# Core_Power_Decoupling.net
KiCad netlist of a schematic drawn in Altium Designer
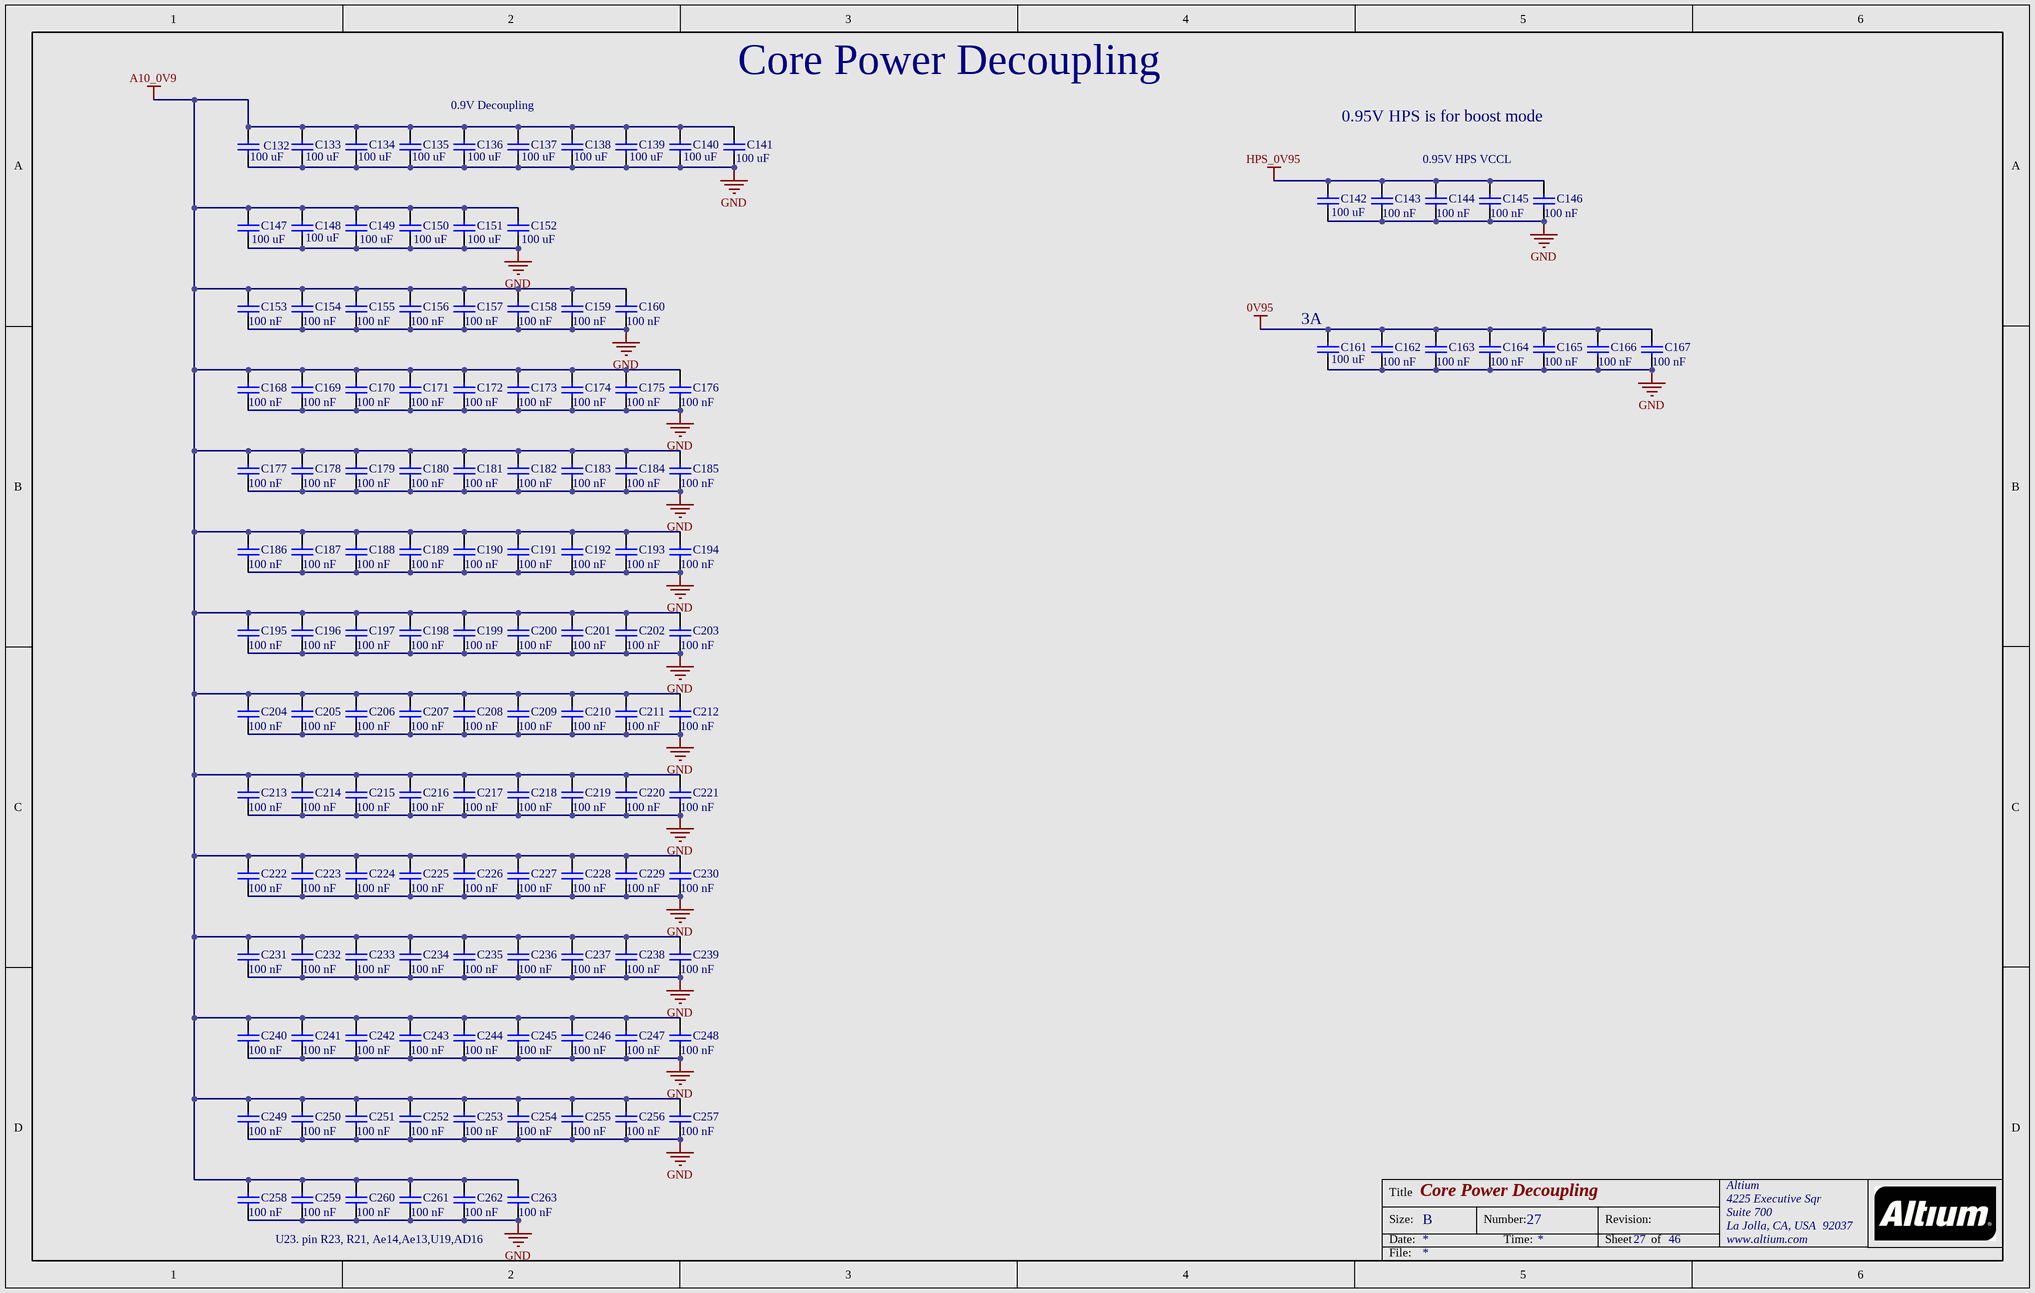
[diagram p0: Core_Power_Decoupling.SchDoc]

(export (version "E")
  (design (tool "Eeschema 10.0.6"))
  (components
    (comp (ref "C132")
      (value "GRM31CR60J107ME39L")
      (footprint "CAPC3216X190X55ML30T25")
      (description "Chip Capacitor, 100 uF, +/- 20%, 6.3 V, -55 to 85 degC, 1206 (3216 Metric), RoHS, Tape and Reel")
      (fields (field (name "TOLERANCE") "20%") (field (name "CAPACITANCE") "100 uF"))
      (libsource (lib "Altium Content Vault") (part "CAP-NP-2"))
    )
    (comp (ref "C133")
      (value "GRM31CR60J107ME39L")
      (footprint "CAPC3216X190X55ML30T25")
      (description "Chip Capacitor, 100 uF, +/- 20%, 6.3 V, -55 to 85 degC, 1206 (3216 Metric), RoHS, Tape and Reel")
      (fields (field (name "TOLERANCE") "20%") (field (name "CAPACITANCE") "100 uF"))
      (libsource (lib "Altium Content Vault") (part "CAP-NP-2"))
    )
    (comp (ref "C134")
      (value "GRM31CR60J107ME39L")
      (footprint "CAPC3216X190X55ML30T25")
      (description "Chip Capacitor, 100 uF, +/- 20%, 6.3 V, -55 to 85 degC, 1206 (3216 Metric), RoHS, Tape and Reel")
      (fields (field (name "TOLERANCE") "20%") (field (name "CAPACITANCE") "100 uF"))
      (libsource (lib "Altium Content Vault") (part "CAP-NP-2"))
    )
    (comp (ref "C135")
      (value "GRM31CR60J107ME39L")
      (footprint "CAPC3216X190X55ML30T25")
      (description "Chip Capacitor, 100 uF, +/- 20%, 6.3 V, -55 to 85 degC, 1206 (3216 Metric), RoHS, Tape and Reel")
      (fields (field (name "TOLERANCE") "20%") (field (name "CAPACITANCE") "100 uF"))
      (libsource (lib "Altium Content Vault") (part "CAP-NP-2"))
    )
    (comp (ref "C136")
      (value "GRM31CR60J107ME39L")
      (footprint "CAPC3216X190X55ML30T25")
      (description "Chip Capacitor, 100 uF, +/- 20%, 6.3 V, -55 to 85 degC, 1206 (3216 Metric), RoHS, Tape and Reel")
      (fields (field (name "TOLERANCE") "20%") (field (name "CAPACITANCE") "100 uF"))
      (libsource (lib "Altium Content Vault") (part "CAP-NP-2"))
    )
    (comp (ref "C137")
      (value "GRM31CR60J107ME39L")
      (footprint "CAPC3216X190X55ML30T25")
      (description "Chip Capacitor, 100 uF, +/- 20%, 6.3 V, -55 to 85 degC, 1206 (3216 Metric), RoHS, Tape and Reel")
      (fields (field (name "TOLERANCE") "20%") (field (name "CAPACITANCE") "100 uF"))
      (libsource (lib "Altium Content Vault") (part "CAP-NP-2"))
    )
    (comp (ref "C138")
      (value "GRM31CR60J107ME39L")
      (footprint "CAPC3216X190X55ML30T25")
      (description "Chip Capacitor, 100 uF, +/- 20%, 6.3 V, -55 to 85 degC, 1206 (3216 Metric), RoHS, Tape and Reel")
      (fields (field (name "TOLERANCE") "20%") (field (name "CAPACITANCE") "100 uF"))
      (libsource (lib "Altium Content Vault") (part "CAP-NP-2"))
    )
    (comp (ref "C139")
      (value "GRM31CR60J107ME39L")
      (footprint "CAPC3216X190X55ML30T25")
      (description "Chip Capacitor, 100 uF, +/- 20%, 6.3 V, -55 to 85 degC, 1206 (3216 Metric), RoHS, Tape and Reel")
      (fields (field (name "TOLERANCE") "20%") (field (name "CAPACITANCE") "100 uF"))
      (libsource (lib "Altium Content Vault") (part "CAP-NP-2"))
    )
    (comp (ref "C140")
      (value "GRM31CR60J107ME39L")
      (footprint "CAPC3216X190X55ML30T25")
      (description "Chip Capacitor, 100 uF, +/- 20%, 6.3 V, -55 to 85 degC, 1206 (3216 Metric), RoHS, Tape and Reel")
      (fields (field (name "TOLERANCE") "20%") (field (name "CAPACITANCE") "100 uF"))
      (libsource (lib "Altium Content Vault") (part "CAP-NP-2"))
    )
    (comp (ref "C141")
      (value "GRM31CR60J107ME39L")
      (footprint "CAPC3216X190X55ML30T25")
      (description "Chip Capacitor, 100 uF, +/- 20%, 6.3 V, -55 to 85 degC, 1206 (3216 Metric), RoHS, Tape and Reel")
      (fields (field (name "TOLERANCE") "20%") (field (name "CAPACITANCE") "100 uF"))
      (libsource (lib "Altium Content Vault") (part "CAP-NP-2"))
    )
    (comp (ref "C142")
      (value "GRM31CR60J107ME39L")
      (footprint "CAPC3216X190X55ML30T25")
      (description "Chip Capacitor, 100 uF, +/- 20%, 6.3 V, -55 to 85 degC, 1206 (3216 Metric), RoHS, Tape and Reel")
      (fields (field (name "TOLERANCE") "20%") (field (name "CAPACITANCE") "100 uF"))
      (libsource (lib "Altium Content Vault") (part "CAP-NP-2"))
    )
    (comp (ref "C143")
      (value "GRM033R60J104KE19D")
      (footprint "CAPC0603X33X15LL03T05")
      (description "Chip Capacitor, 100 nF, +/- 10%, 6.3 V, -55 to 85 degC, 0201 (0603 Metric), RoHS, Tape and Reel")
      (fields
        (field (name "TOLERANCE") "10%")
        (field (name "CAPACITANCE") "100 nF")
        (field (name "MANUFACTURER") "Basic Passives")
      )
      (libsource (lib "Altium Content Vault") (part "CAP-NP-2"))
    )
    (comp (ref "C144")
      (value "GRM033R60J104KE19D")
      (footprint "CAPC0603X33X15LL03T05")
      (description "Chip Capacitor, 100 nF, +/- 10%, 6.3 V, -55 to 85 degC, 0201 (0603 Metric), RoHS, Tape and Reel")
      (fields
        (field (name "TOLERANCE") "10%")
        (field (name "CAPACITANCE") "100 nF")
        (field (name "MANUFACTURER") "Basic Passives")
      )
      (libsource (lib "Altium Content Vault") (part "CAP-NP-2"))
    )
    (comp (ref "C145")
      (value "GRM033R60J104KE19D")
      (footprint "CAPC0603X33X15LL03T05")
      (description "Chip Capacitor, 100 nF, +/- 10%, 6.3 V, -55 to 85 degC, 0201 (0603 Metric), RoHS, Tape and Reel")
      (fields
        (field (name "TOLERANCE") "10%")
        (field (name "CAPACITANCE") "100 nF")
        (field (name "MANUFACTURER") "Basic Passives")
      )
      (libsource (lib "Altium Content Vault") (part "CAP-NP-2"))
    )
    (comp (ref "C146")
      (value "GRM033R60J104KE19D")
      (footprint "CAPC0603X33X15LL03T05")
      (description "Chip Capacitor, 100 nF, +/- 10%, 6.3 V, -55 to 85 degC, 0201 (0603 Metric), RoHS, Tape and Reel")
      (fields
        (field (name "TOLERANCE") "10%")
        (field (name "CAPACITANCE") "100 nF")
        (field (name "MANUFACTURER") "Basic Passives")
      )
      (libsource (lib "Altium Content Vault") (part "CAP-NP-2"))
    )
    (comp (ref "C147")
      (value "GRM31CR60J107ME39L")
      (footprint "CAPC3216X190X55ML30T25")
      (description "Chip Capacitor, 100 uF, +/- 20%, 6.3 V, -55 to 85 degC, 1206 (3216 Metric), RoHS, Tape and Reel")
      (fields (field (name "TOLERANCE") "20%") (field (name "CAPACITANCE") "100 uF"))
      (libsource (lib "Altium Content Vault") (part "CAP-NP-2"))
    )
    (comp (ref "C148")
      (value "GRM31CR60J107ME39L")
      (footprint "CAPC3216X190X55ML30T25")
      (description "Chip Capacitor, 100 uF, +/- 20%, 6.3 V, -55 to 85 degC, 1206 (3216 Metric), RoHS, Tape and Reel")
      (fields (field (name "TOLERANCE") "20%") (field (name "CAPACITANCE") "100 uF"))
      (libsource (lib "Altium Content Vault") (part "CAP-NP-2"))
    )
    (comp (ref "C149")
      (value "GRM31CR60J107ME39L")
      (footprint "CAPC3216X190X55ML30T25")
      (description "Chip Capacitor, 100 uF, +/- 20%, 6.3 V, -55 to 85 degC, 1206 (3216 Metric), RoHS, Tape and Reel")
      (fields (field (name "TOLERANCE") "20%") (field (name "CAPACITANCE") "100 uF"))
      (libsource (lib "Altium Content Vault") (part "CAP-NP-2"))
    )
    (comp (ref "C150")
      (value "GRM31CR60J107ME39L")
      (footprint "CAPC3216X190X55ML30T25")
      (description "Chip Capacitor, 100 uF, +/- 20%, 6.3 V, -55 to 85 degC, 1206 (3216 Metric), RoHS, Tape and Reel")
      (fields (field (name "TOLERANCE") "20%") (field (name "CAPACITANCE") "100 uF"))
      (libsource (lib "Altium Content Vault") (part "CAP-NP-2"))
    )
    (comp (ref "C151")
      (value "GRM31CR60J107ME39L")
      (footprint "CAPC3216X190X55ML30T25")
      (description "Chip Capacitor, 100 uF, +/- 20%, 6.3 V, -55 to 85 degC, 1206 (3216 Metric), RoHS, Tape and Reel")
      (fields (field (name "TOLERANCE") "20%") (field (name "CAPACITANCE") "100 uF"))
      (libsource (lib "Altium Content Vault") (part "CAP-NP-2"))
    )
    (comp (ref "C152")
      (value "GRM31CR60J107ME39L")
      (footprint "CAPC3216X190X55ML30T25")
      (description "Chip Capacitor, 100 uF, +/- 20%, 6.3 V, -55 to 85 degC, 1206 (3216 Metric), RoHS, Tape and Reel")
      (fields (field (name "TOLERANCE") "20%") (field (name "CAPACITANCE") "100 uF"))
      (libsource (lib "Altium Content Vault") (part "CAP-NP-2"))
    )
    (comp (ref "C153")
      (value "GRM033R60J104KE19D")
      (footprint "CAPC0603X33X15LL03T05")
      (description "Chip Capacitor, 100 nF, +/- 10%, 6.3 V, -55 to 85 degC, 0201 (0603 Metric), RoHS, Tape and Reel")
      (fields
        (field (name "TOLERANCE") "10%")
        (field (name "CAPACITANCE") "100 nF")
        (field (name "MANUFACTURER") "Basic Passives")
      )
      (libsource (lib "Altium Content Vault") (part "CAP-NP-2"))
    )
    (comp (ref "C154")
      (value "GRM033R60J104KE19D")
      (footprint "CAPC0603X33X15LL03T05")
      (description "Chip Capacitor, 100 nF, +/- 10%, 6.3 V, -55 to 85 degC, 0201 (0603 Metric), RoHS, Tape and Reel")
      (fields
        (field (name "TOLERANCE") "10%")
        (field (name "CAPACITANCE") "100 nF")
        (field (name "MANUFACTURER") "Basic Passives")
      )
      (libsource (lib "Altium Content Vault") (part "CAP-NP-2"))
    )
    (comp (ref "C155")
      (value "GRM033R60J104KE19D")
      (footprint "CAPC0603X33X15LL03T05")
      (description "Chip Capacitor, 100 nF, +/- 10%, 6.3 V, -55 to 85 degC, 0201 (0603 Metric), RoHS, Tape and Reel")
      (fields
        (field (name "TOLERANCE") "10%")
        (field (name "CAPACITANCE") "100 nF")
        (field (name "MANUFACTURER") "Basic Passives")
      )
      (libsource (lib "Altium Content Vault") (part "CAP-NP-2"))
    )
    (comp (ref "C156")
      (value "GRM033R60J104KE19D")
      (footprint "CAPC0603X33X15LL03T05")
      (description "Chip Capacitor, 100 nF, +/- 10%, 6.3 V, -55 to 85 degC, 0201 (0603 Metric), RoHS, Tape and Reel")
      (fields
        (field (name "TOLERANCE") "10%")
        (field (name "CAPACITANCE") "100 nF")
        (field (name "MANUFACTURER") "Basic Passives")
      )
      (libsource (lib "Altium Content Vault") (part "CAP-NP-2"))
    )
    (comp (ref "C157")
      (value "GRM033R60J104KE19D")
      (footprint "CAPC0603X33X15LL03T05")
      (description "Chip Capacitor, 100 nF, +/- 10%, 6.3 V, -55 to 85 degC, 0201 (0603 Metric), RoHS, Tape and Reel")
      (fields
        (field (name "TOLERANCE") "10%")
        (field (name "CAPACITANCE") "100 nF")
        (field (name "MANUFACTURER") "Basic Passives")
      )
      (libsource (lib "Altium Content Vault") (part "CAP-NP-2"))
    )
    (comp (ref "C158")
      (value "GRM033R60J104KE19D")
      (footprint "CAPC0603X33X15LL03T05")
      (description "Chip Capacitor, 100 nF, +/- 10%, 6.3 V, -55 to 85 degC, 0201 (0603 Metric), RoHS, Tape and Reel")
      (fields
        (field (name "TOLERANCE") "10%")
        (field (name "CAPACITANCE") "100 nF")
        (field (name "MANUFACTURER") "Basic Passives")
      )
      (libsource (lib "Altium Content Vault") (part "CAP-NP-2"))
    )
    (comp (ref "C159")
      (value "GRM033R60J104KE19D")
      (footprint "CAPC0603X33X15LL03T05")
      (description "Chip Capacitor, 100 nF, +/- 10%, 6.3 V, -55 to 85 degC, 0201 (0603 Metric), RoHS, Tape and Reel")
      (fields
        (field (name "TOLERANCE") "10%")
        (field (name "CAPACITANCE") "100 nF")
        (field (name "MANUFACTURER") "Basic Passives")
      )
      (libsource (lib "Altium Content Vault") (part "CAP-NP-2"))
    )
    (comp (ref "C160")
      (value "GRM033R60J104KE19D")
      (footprint "CAPC0603X33X15LL03T05")
      (description "Chip Capacitor, 100 nF, +/- 10%, 6.3 V, -55 to 85 degC, 0201 (0603 Metric), RoHS, Tape and Reel")
      (fields
        (field (name "TOLERANCE") "10%")
        (field (name "CAPACITANCE") "100 nF")
        (field (name "MANUFACTURER") "Basic Passives")
      )
      (libsource (lib "Altium Content Vault") (part "CAP-NP-2"))
    )
    (comp (ref "C161")
      (value "GRM31CR60J107ME39L")
      (footprint "CAPC3216X190X55ML30T25")
      (description "Chip Capacitor, 100 uF, +/- 20%, 6.3 V, -55 to 85 degC, 1206 (3216 Metric), RoHS, Tape and Reel")
      (fields (field (name "TOLERANCE") "20%") (field (name "CAPACITANCE") "100 uF"))
      (libsource (lib "Altium Content Vault") (part "CAP-NP-2"))
    )
    (comp (ref "C162")
      (value "GRM033R60J104KE19D")
      (footprint "CAPC0603X33X15LL03T05")
      (description "Chip Capacitor, 100 nF, +/- 10%, 6.3 V, -55 to 85 degC, 0201 (0603 Metric), RoHS, Tape and Reel")
      (fields
        (field (name "TOLERANCE") "10%")
        (field (name "CAPACITANCE") "100 nF")
        (field (name "MANUFACTURER") "Basic Passives")
      )
      (libsource (lib "Altium Content Vault") (part "CAP-NP-2"))
    )
    (comp (ref "C163")
      (value "GRM033R60J104KE19D")
      (footprint "CAPC0603X33X15LL03T05")
      (description "Chip Capacitor, 100 nF, +/- 10%, 6.3 V, -55 to 85 degC, 0201 (0603 Metric), RoHS, Tape and Reel")
      (fields
        (field (name "TOLERANCE") "10%")
        (field (name "CAPACITANCE") "100 nF")
        (field (name "MANUFACTURER") "Basic Passives")
      )
      (libsource (lib "Altium Content Vault") (part "CAP-NP-2"))
    )
    (comp (ref "C164")
      (value "GRM033R60J104KE19D")
      (footprint "CAPC0603X33X15LL03T05")
      (description "Chip Capacitor, 100 nF, +/- 10%, 6.3 V, -55 to 85 degC, 0201 (0603 Metric), RoHS, Tape and Reel")
      (fields
        (field (name "TOLERANCE") "10%")
        (field (name "CAPACITANCE") "100 nF")
        (field (name "MANUFACTURER") "Basic Passives")
      )
      (libsource (lib "Altium Content Vault") (part "CAP-NP-2"))
    )
    (comp (ref "C165")
      (value "GRM033R60J104KE19D")
      (footprint "CAPC0603X33X15LL03T05")
      (description "Chip Capacitor, 100 nF, +/- 10%, 6.3 V, -55 to 85 degC, 0201 (0603 Metric), RoHS, Tape and Reel")
      (fields
        (field (name "TOLERANCE") "10%")
        (field (name "CAPACITANCE") "100 nF")
        (field (name "MANUFACTURER") "Basic Passives")
      )
      (libsource (lib "Altium Content Vault") (part "CAP-NP-2"))
    )
    (comp (ref "C166")
      (value "GRM033R60J104KE19D")
      (footprint "CAPC0603X33X15LL03T05")
      (description "Chip Capacitor, 100 nF, +/- 10%, 6.3 V, -55 to 85 degC, 0201 (0603 Metric), RoHS, Tape and Reel")
      (fields
        (field (name "TOLERANCE") "10%")
        (field (name "CAPACITANCE") "100 nF")
        (field (name "MANUFACTURER") "Basic Passives")
      )
      (libsource (lib "Altium Content Vault") (part "CAP-NP-2"))
    )
    (comp (ref "C167")
      (value "GRM033R60J104KE19D")
      (footprint "CAPC0603X33X15LL03T05")
      (description "Chip Capacitor, 100 nF, +/- 10%, 6.3 V, -55 to 85 degC, 0201 (0603 Metric), RoHS, Tape and Reel")
      (fields
        (field (name "TOLERANCE") "10%")
        (field (name "CAPACITANCE") "100 nF")
        (field (name "MANUFACTURER") "Basic Passives")
      )
      (libsource (lib "Altium Content Vault") (part "CAP-NP-2"))
    )
    (comp (ref "C168")
      (value "GRM033R60J104KE19D")
      (footprint "CAPC0603X33X15LL03T05")
      (description "Chip Capacitor, 100 nF, +/- 10%, 6.3 V, -55 to 85 degC, 0201 (0603 Metric), RoHS, Tape and Reel")
      (fields
        (field (name "TOLERANCE") "10%")
        (field (name "CAPACITANCE") "100 nF")
        (field (name "MANUFACTURER") "Basic Passives")
      )
      (libsource (lib "Altium Content Vault") (part "CAP-NP-2"))
    )
    (comp (ref "C169")
      (value "GRM033R60J104KE19D")
      (footprint "CAPC0603X33X15LL03T05")
      (description "Chip Capacitor, 100 nF, +/- 10%, 6.3 V, -55 to 85 degC, 0201 (0603 Metric), RoHS, Tape and Reel")
      (fields
        (field (name "TOLERANCE") "10%")
        (field (name "CAPACITANCE") "100 nF")
        (field (name "MANUFACTURER") "Basic Passives")
      )
      (libsource (lib "Altium Content Vault") (part "CAP-NP-2"))
    )
    (comp (ref "C170")
      (value "GRM033R60J104KE19D")
      (footprint "CAPC0603X33X15LL03T05")
      (description "Chip Capacitor, 100 nF, +/- 10%, 6.3 V, -55 to 85 degC, 0201 (0603 Metric), RoHS, Tape and Reel")
      (fields
        (field (name "TOLERANCE") "10%")
        (field (name "CAPACITANCE") "100 nF")
        (field (name "MANUFACTURER") "Basic Passives")
      )
      (libsource (lib "Altium Content Vault") (part "CAP-NP-2"))
    )
    (comp (ref "C171")
      (value "GRM033R60J104KE19D")
      (footprint "CAPC0603X33X15LL03T05")
      (description "Chip Capacitor, 100 nF, +/- 10%, 6.3 V, -55 to 85 degC, 0201 (0603 Metric), RoHS, Tape and Reel")
      (fields
        (field (name "TOLERANCE") "10%")
        (field (name "CAPACITANCE") "100 nF")
        (field (name "MANUFACTURER") "Basic Passives")
      )
      (libsource (lib "Altium Content Vault") (part "CAP-NP-2"))
    )
    (comp (ref "C172")
      (value "GRM033R60J104KE19D")
      (footprint "CAPC0603X33X15LL03T05")
      (description "Chip Capacitor, 100 nF, +/- 10%, 6.3 V, -55 to 85 degC, 0201 (0603 Metric), RoHS, Tape and Reel")
      (fields
        (field (name "TOLERANCE") "10%")
        (field (name "CAPACITANCE") "100 nF")
        (field (name "MANUFACTURER") "Basic Passives")
      )
      (libsource (lib "Altium Content Vault") (part "CAP-NP-2"))
    )
    (comp (ref "C173")
      (value "GRM033R60J104KE19D")
      (footprint "CAPC0603X33X15LL03T05")
      (description "Chip Capacitor, 100 nF, +/- 10%, 6.3 V, -55 to 85 degC, 0201 (0603 Metric), RoHS, Tape and Reel")
      (fields
        (field (name "TOLERANCE") "10%")
        (field (name "CAPACITANCE") "100 nF")
        (field (name "MANUFACTURER") "Basic Passives")
      )
      (libsource (lib "Altium Content Vault") (part "CAP-NP-2"))
    )
    (comp (ref "C174")
      (value "GRM033R60J104KE19D")
      (footprint "CAPC0603X33X15LL03T05")
      (description "Chip Capacitor, 100 nF, +/- 10%, 6.3 V, -55 to 85 degC, 0201 (0603 Metric), RoHS, Tape and Reel")
      (fields
        (field (name "TOLERANCE") "10%")
        (field (name "CAPACITANCE") "100 nF")
        (field (name "MANUFACTURER") "Basic Passives")
      )
      (libsource (lib "Altium Content Vault") (part "CAP-NP-2"))
    )
    (comp (ref "C175")
      (value "GRM033R60J104KE19D")
      (footprint "CAPC0603X33X15LL03T05")
      (description "Chip Capacitor, 100 nF, +/- 10%, 6.3 V, -55 to 85 degC, 0201 (0603 Metric), RoHS, Tape and Reel")
      (fields
        (field (name "TOLERANCE") "10%")
        (field (name "CAPACITANCE") "100 nF")
        (field (name "MANUFACTURER") "Basic Passives")
      )
      (libsource (lib "Altium Content Vault") (part "CAP-NP-2"))
    )
    (comp (ref "C176")
      (value "GRM033R60J104KE19D")
      (footprint "CAPC0603X33X15LL03T05")
      (description "Chip Capacitor, 100 nF, +/- 10%, 6.3 V, -55 to 85 degC, 0201 (0603 Metric), RoHS, Tape and Reel")
      (fields
        (field (name "TOLERANCE") "10%")
        (field (name "CAPACITANCE") "100 nF")
        (field (name "MANUFACTURER") "Basic Passives")
      )
      (libsource (lib "Altium Content Vault") (part "CAP-NP-2"))
    )
    (comp (ref "C177")
      (value "GRM033R60J104KE19D")
      (footprint "CAPC0603X33X15LL03T05")
      (description "Chip Capacitor, 100 nF, +/- 10%, 6.3 V, -55 to 85 degC, 0201 (0603 Metric), RoHS, Tape and Reel")
      (fields
        (field (name "TOLERANCE") "10%")
        (field (name "CAPACITANCE") "100 nF")
        (field (name "MANUFACTURER") "Basic Passives")
      )
      (libsource (lib "Altium Content Vault") (part "CAP-NP-2"))
    )
    (comp (ref "C178")
      (value "GRM033R60J104KE19D")
      (footprint "CAPC0603X33X15LL03T05")
      (description "Chip Capacitor, 100 nF, +/- 10%, 6.3 V, -55 to 85 degC, 0201 (0603 Metric), RoHS, Tape and Reel")
      (fields
        (field (name "TOLERANCE") "10%")
        (field (name "CAPACITANCE") "100 nF")
        (field (name "MANUFACTURER") "Basic Passives")
      )
      (libsource (lib "Altium Content Vault") (part "CAP-NP-2"))
    )
    (comp (ref "C179")
      (value "GRM033R60J104KE19D")
      (footprint "CAPC0603X33X15LL03T05")
      (description "Chip Capacitor, 100 nF, +/- 10%, 6.3 V, -55 to 85 degC, 0201 (0603 Metric), RoHS, Tape and Reel")
      (fields
        (field (name "TOLERANCE") "10%")
        (field (name "CAPACITANCE") "100 nF")
        (field (name "MANUFACTURER") "Basic Passives")
      )
      (libsource (lib "Altium Content Vault") (part "CAP-NP-2"))
    )
    (comp (ref "C180")
      (value "GRM033R60J104KE19D")
      (footprint "CAPC0603X33X15LL03T05")
      (description "Chip Capacitor, 100 nF, +/- 10%, 6.3 V, -55 to 85 degC, 0201 (0603 Metric), RoHS, Tape and Reel")
      (fields
        (field (name "TOLERANCE") "10%")
        (field (name "CAPACITANCE") "100 nF")
        (field (name "MANUFACTURER") "Basic Passives")
      )
      (libsource (lib "Altium Content Vault") (part "CAP-NP-2"))
    )
    (comp (ref "C181")
      (value "GRM033R60J104KE19D")
      (footprint "CAPC0603X33X15LL03T05")
      (description "Chip Capacitor, 100 nF, +/- 10%, 6.3 V, -55 to 85 degC, 0201 (0603 Metric), RoHS, Tape and Reel")
      (fields
        (field (name "TOLERANCE") "10%")
        (field (name "CAPACITANCE") "100 nF")
        (field (name "MANUFACTURER") "Basic Passives")
      )
      (libsource (lib "Altium Content Vault") (part "CAP-NP-2"))
    )
    (comp (ref "C182")
      (value "GRM033R60J104KE19D")
      (footprint "CAPC0603X33X15LL03T05")
      (description "Chip Capacitor, 100 nF, +/- 10%, 6.3 V, -55 to 85 degC, 0201 (0603 Metric), RoHS, Tape and Reel")
      (fields
        (field (name "TOLERANCE") "10%")
        (field (name "CAPACITANCE") "100 nF")
        (field (name "MANUFACTURER") "Basic Passives")
      )
      (libsource (lib "Altium Content Vault") (part "CAP-NP-2"))
    )
    (comp (ref "C183")
      (value "GRM033R60J104KE19D")
      (footprint "CAPC0603X33X15LL03T05")
      (description "Chip Capacitor, 100 nF, +/- 10%, 6.3 V, -55 to 85 degC, 0201 (0603 Metric), RoHS, Tape and Reel")
      (fields
        (field (name "TOLERANCE") "10%")
        (field (name "CAPACITANCE") "100 nF")
        (field (name "MANUFACTURER") "Basic Passives")
      )
      (libsource (lib "Altium Content Vault") (part "CAP-NP-2"))
    )
    (comp (ref "C184")
      (value "GRM033R60J104KE19D")
      (footprint "CAPC0603X33X15LL03T05")
      (description "Chip Capacitor, 100 nF, +/- 10%, 6.3 V, -55 to 85 degC, 0201 (0603 Metric), RoHS, Tape and Reel")
      (fields
        (field (name "TOLERANCE") "10%")
        (field (name "CAPACITANCE") "100 nF")
        (field (name "MANUFACTURER") "Basic Passives")
      )
      (libsource (lib "Altium Content Vault") (part "CAP-NP-2"))
    )
    (comp (ref "C185")
      (value "GRM033R60J104KE19D")
      (footprint "CAPC0603X33X15LL03T05")
      (description "Chip Capacitor, 100 nF, +/- 10%, 6.3 V, -55 to 85 degC, 0201 (0603 Metric), RoHS, Tape and Reel")
      (fields
        (field (name "TOLERANCE") "10%")
        (field (name "CAPACITANCE") "100 nF")
        (field (name "MANUFACTURER") "Basic Passives")
      )
      (libsource (lib "Altium Content Vault") (part "CAP-NP-2"))
    )
    (comp (ref "C186")
      (value "GRM033R60J104KE19D")
      (footprint "CAPC0603X33X15LL03T05")
      (description "Chip Capacitor, 100 nF, +/- 10%, 6.3 V, -55 to 85 degC, 0201 (0603 Metric), RoHS, Tape and Reel")
      (fields
        (field (name "TOLERANCE") "10%")
        (field (name "CAPACITANCE") "100 nF")
        (field (name "MANUFACTURER") "Basic Passives")
      )
      (libsource (lib "Altium Content Vault") (part "CAP-NP-2"))
    )
    (comp (ref "C187")
      (value "GRM033R60J104KE19D")
      (footprint "CAPC0603X33X15LL03T05")
      (description "Chip Capacitor, 100 nF, +/- 10%, 6.3 V, -55 to 85 degC, 0201 (0603 Metric), RoHS, Tape and Reel")
      (fields
        (field (name "TOLERANCE") "10%")
        (field (name "CAPACITANCE") "100 nF")
        (field (name "MANUFACTURER") "Basic Passives")
      )
      (libsource (lib "Altium Content Vault") (part "CAP-NP-2"))
    )
    (comp (ref "C188")
      (value "GRM033R60J104KE19D")
      (footprint "CAPC0603X33X15LL03T05")
      (description "Chip Capacitor, 100 nF, +/- 10%, 6.3 V, -55 to 85 degC, 0201 (0603 Metric), RoHS, Tape and Reel")
      (fields
        (field (name "TOLERANCE") "10%")
        (field (name "CAPACITANCE") "100 nF")
        (field (name "MANUFACTURER") "Basic Passives")
      )
      (libsource (lib "Altium Content Vault") (part "CAP-NP-2"))
    )
    (comp (ref "C189")
      (value "GRM033R60J104KE19D")
      (footprint "CAPC0603X33X15LL03T05")
      (description "Chip Capacitor, 100 nF, +/- 10%, 6.3 V, -55 to 85 degC, 0201 (0603 Metric), RoHS, Tape and Reel")
      (fields
        (field (name "TOLERANCE") "10%")
        (field (name "CAPACITANCE") "100 nF")
        (field (name "MANUFACTURER") "Basic Passives")
      )
      (libsource (lib "Altium Content Vault") (part "CAP-NP-2"))
    )
    (comp (ref "C190")
      (value "GRM033R60J104KE19D")
      (footprint "CAPC0603X33X15LL03T05")
      (description "Chip Capacitor, 100 nF, +/- 10%, 6.3 V, -55 to 85 degC, 0201 (0603 Metric), RoHS, Tape and Reel")
      (fields
        (field (name "TOLERANCE") "10%")
        (field (name "CAPACITANCE") "100 nF")
        (field (name "MANUFACTURER") "Basic Passives")
      )
      (libsource (lib "Altium Content Vault") (part "CAP-NP-2"))
    )
    (comp (ref "C191")
      (value "GRM033R60J104KE19D")
      (footprint "CAPC0603X33X15LL03T05")
      (description "Chip Capacitor, 100 nF, +/- 10%, 6.3 V, -55 to 85 degC, 0201 (0603 Metric), RoHS, Tape and Reel")
      (fields
        (field (name "TOLERANCE") "10%")
        (field (name "CAPACITANCE") "100 nF")
        (field (name "MANUFACTURER") "Basic Passives")
      )
      (libsource (lib "Altium Content Vault") (part "CAP-NP-2"))
    )
    (comp (ref "C192")
      (value "GRM033R60J104KE19D")
      (footprint "CAPC0603X33X15LL03T05")
      (description "Chip Capacitor, 100 nF, +/- 10%, 6.3 V, -55 to 85 degC, 0201 (0603 Metric), RoHS, Tape and Reel")
      (fields
        (field (name "TOLERANCE") "10%")
        (field (name "CAPACITANCE") "100 nF")
        (field (name "MANUFACTURER") "Basic Passives")
      )
      (libsource (lib "Altium Content Vault") (part "CAP-NP-2"))
    )
    (comp (ref "C193")
      (value "GRM033R60J104KE19D")
      (footprint "CAPC0603X33X15LL03T05")
      (description "Chip Capacitor, 100 nF, +/- 10%, 6.3 V, -55 to 85 degC, 0201 (0603 Metric), RoHS, Tape and Reel")
      (fields
        (field (name "TOLERANCE") "10%")
        (field (name "CAPACITANCE") "100 nF")
        (field (name "MANUFACTURER") "Basic Passives")
      )
      (libsource (lib "Altium Content Vault") (part "CAP-NP-2"))
    )
    (comp (ref "C194")
      (value "GRM033R60J104KE19D")
      (footprint "CAPC0603X33X15LL03T05")
      (description "Chip Capacitor, 100 nF, +/- 10%, 6.3 V, -55 to 85 degC, 0201 (0603 Metric), RoHS, Tape and Reel")
      (fields
        (field (name "TOLERANCE") "10%")
        (field (name "CAPACITANCE") "100 nF")
        (field (name "MANUFACTURER") "Basic Passives")
      )
      (libsource (lib "Altium Content Vault") (part "CAP-NP-2"))
    )
    (comp (ref "C195")
      (value "GRM033R60J104KE19D")
      (footprint "CAPC0603X33X15LL03T05")
      (description "Chip Capacitor, 100 nF, +/- 10%, 6.3 V, -55 to 85 degC, 0201 (0603 Metric), RoHS, Tape and Reel")
      (fields
        (field (name "TOLERANCE") "10%")
        (field (name "CAPACITANCE") "100 nF")
        (field (name "MANUFACTURER") "Basic Passives")
      )
      (libsource (lib "Altium Content Vault") (part "CAP-NP-2"))
    )
    (comp (ref "C196")
      (value "GRM033R60J104KE19D")
      (footprint "CAPC0603X33X15LL03T05")
      (description "Chip Capacitor, 100 nF, +/- 10%, 6.3 V, -55 to 85 degC, 0201 (0603 Metric), RoHS, Tape and Reel")
      (fields
        (field (name "TOLERANCE") "10%")
        (field (name "CAPACITANCE") "100 nF")
        (field (name "MANUFACTURER") "Basic Passives")
      )
      (libsource (lib "Altium Content Vault") (part "CAP-NP-2"))
    )
    (comp (ref "C197")
      (value "GRM033R60J104KE19D")
      (footprint "CAPC0603X33X15LL03T05")
      (description "Chip Capacitor, 100 nF, +/- 10%, 6.3 V, -55 to 85 degC, 0201 (0603 Metric), RoHS, Tape and Reel")
      (fields
        (field (name "TOLERANCE") "10%")
        (field (name "CAPACITANCE") "100 nF")
        (field (name "MANUFACTURER") "Basic Passives")
      )
      (libsource (lib "Altium Content Vault") (part "CAP-NP-2"))
    )
    (comp (ref "C198")
      (value "GRM033R60J104KE19D")
      (footprint "CAPC0603X33X15LL03T05")
      (description "Chip Capacitor, 100 nF, +/- 10%, 6.3 V, -55 to 85 degC, 0201 (0603 Metric), RoHS, Tape and Reel")
      (fields
        (field (name "TOLERANCE") "10%")
        (field (name "CAPACITANCE") "100 nF")
        (field (name "MANUFACTURER") "Basic Passives")
      )
      (libsource (lib "Altium Content Vault") (part "CAP-NP-2"))
    )
    (comp (ref "C199")
      (value "GRM033R60J104KE19D")
      (footprint "CAPC0603X33X15LL03T05")
      (description "Chip Capacitor, 100 nF, +/- 10%, 6.3 V, -55 to 85 degC, 0201 (0603 Metric), RoHS, Tape and Reel")
      (fields
        (field (name "TOLERANCE") "10%")
        (field (name "CAPACITANCE") "100 nF")
        (field (name "MANUFACTURER") "Basic Passives")
      )
      (libsource (lib "Altium Content Vault") (part "CAP-NP-2"))
    )
    (comp (ref "C200")
      (value "GRM033R60J104KE19D")
      (footprint "CAPC0603X33X15LL03T05")
      (description "Chip Capacitor, 100 nF, +/- 10%, 6.3 V, -55 to 85 degC, 0201 (0603 Metric), RoHS, Tape and Reel")
      (fields
        (field (name "TOLERANCE") "10%")
        (field (name "CAPACITANCE") "100 nF")
        (field (name "MANUFACTURER") "Basic Passives")
      )
      (libsource (lib "Altium Content Vault") (part "CAP-NP-2"))
    )
    (comp (ref "C201")
      (value "GRM033R60J104KE19D")
      (footprint "CAPC0603X33X15LL03T05")
      (description "Chip Capacitor, 100 nF, +/- 10%, 6.3 V, -55 to 85 degC, 0201 (0603 Metric), RoHS, Tape and Reel")
      (fields
        (field (name "TOLERANCE") "10%")
        (field (name "CAPACITANCE") "100 nF")
        (field (name "MANUFACTURER") "Basic Passives")
      )
      (libsource (lib "Altium Content Vault") (part "CAP-NP-2"))
    )
    (comp (ref "C202")
      (value "GRM033R60J104KE19D")
      (footprint "CAPC0603X33X15LL03T05")
      (description "Chip Capacitor, 100 nF, +/- 10%, 6.3 V, -55 to 85 degC, 0201 (0603 Metric), RoHS, Tape and Reel")
      (fields
        (field (name "TOLERANCE") "10%")
        (field (name "CAPACITANCE") "100 nF")
        (field (name "MANUFACTURER") "Basic Passives")
      )
      (libsource (lib "Altium Content Vault") (part "CAP-NP-2"))
    )
    (comp (ref "C203")
      (value "GRM033R60J104KE19D")
      (footprint "CAPC0603X33X15LL03T05")
      (description "Chip Capacitor, 100 nF, +/- 10%, 6.3 V, -55 to 85 degC, 0201 (0603 Metric), RoHS, Tape and Reel")
      (fields
        (field (name "TOLERANCE") "10%")
        (field (name "CAPACITANCE") "100 nF")
        (field (name "MANUFACTURER") "Basic Passives")
      )
      (libsource (lib "Altium Content Vault") (part "CAP-NP-2"))
    )
    (comp (ref "C204")
      (value "GRM033R60J104KE19D")
      (footprint "CAPC0603X33X15LL03T05")
      (description "Chip Capacitor, 100 nF, +/- 10%, 6.3 V, -55 to 85 degC, 0201 (0603 Metric), RoHS, Tape and Reel")
      (fields
        (field (name "TOLERANCE") "10%")
        (field (name "CAPACITANCE") "100 nF")
        (field (name "MANUFACTURER") "Basic Passives")
      )
      (libsource (lib "Altium Content Vault") (part "CAP-NP-2"))
    )
    (comp (ref "C205")
      (value "GRM033R60J104KE19D")
      (footprint "CAPC0603X33X15LL03T05")
      (description "Chip Capacitor, 100 nF, +/- 10%, 6.3 V, -55 to 85 degC, 0201 (0603 Metric), RoHS, Tape and Reel")
      (fields
        (field (name "TOLERANCE") "10%")
        (field (name "CAPACITANCE") "100 nF")
        (field (name "MANUFACTURER") "Basic Passives")
      )
      (libsource (lib "Altium Content Vault") (part "CAP-NP-2"))
    )
    (comp (ref "C206")
      (value "GRM033R60J104KE19D")
      (footprint "CAPC0603X33X15LL03T05")
      (description "Chip Capacitor, 100 nF, +/- 10%, 6.3 V, -55 to 85 degC, 0201 (0603 Metric), RoHS, Tape and Reel")
      (fields
        (field (name "TOLERANCE") "10%")
        (field (name "CAPACITANCE") "100 nF")
        (field (name "MANUFACTURER") "Basic Passives")
      )
      (libsource (lib "Altium Content Vault") (part "CAP-NP-2"))
    )
    (comp (ref "C207")
      (value "GRM033R60J104KE19D")
      (footprint "CAPC0603X33X15LL03T05")
      (description "Chip Capacitor, 100 nF, +/- 10%, 6.3 V, -55 to 85 degC, 0201 (0603 Metric), RoHS, Tape and Reel")
      (fields
        (field (name "TOLERANCE") "10%")
        (field (name "CAPACITANCE") "100 nF")
        (field (name "MANUFACTURER") "Basic Passives")
      )
      (libsource (lib "Altium Content Vault") (part "CAP-NP-2"))
    )
    (comp (ref "C208")
      (value "GRM033R60J104KE19D")
      (footprint "CAPC0603X33X15LL03T05")
      (description "Chip Capacitor, 100 nF, +/- 10%, 6.3 V, -55 to 85 degC, 0201 (0603 Metric), RoHS, Tape and Reel")
      (fields
        (field (name "TOLERANCE") "10%")
        (field (name "CAPACITANCE") "100 nF")
        (field (name "MANUFACTURER") "Basic Passives")
      )
      (libsource (lib "Altium Content Vault") (part "CAP-NP-2"))
    )
    (comp (ref "C209")
      (value "GRM033R60J104KE19D")
      (footprint "CAPC0603X33X15LL03T05")
      (description "Chip Capacitor, 100 nF, +/- 10%, 6.3 V, -55 to 85 degC, 0201 (0603 Metric), RoHS, Tape and Reel")
      (fields
        (field (name "TOLERANCE") "10%")
        (field (name "CAPACITANCE") "100 nF")
        (field (name "MANUFACTURER") "Basic Passives")
      )
      (libsource (lib "Altium Content Vault") (part "CAP-NP-2"))
    )
    (comp (ref "C210")
      (value "GRM033R60J104KE19D")
      (footprint "CAPC0603X33X15LL03T05")
      (description "Chip Capacitor, 100 nF, +/- 10%, 6.3 V, -55 to 85 degC, 0201 (0603 Metric), RoHS, Tape and Reel")
      (fields
        (field (name "TOLERANCE") "10%")
        (field (name "CAPACITANCE") "100 nF")
        (field (name "MANUFACTURER") "Basic Passives")
      )
      (libsource (lib "Altium Content Vault") (part "CAP-NP-2"))
    )
    (comp (ref "C211")
      (value "GRM033R60J104KE19D")
      (footprint "CAPC0603X33X15LL03T05")
      (description "Chip Capacitor, 100 nF, +/- 10%, 6.3 V, -55 to 85 degC, 0201 (0603 Metric), RoHS, Tape and Reel")
      (fields
        (field (name "TOLERANCE") "10%")
        (field (name "CAPACITANCE") "100 nF")
        (field (name "MANUFACTURER") "Basic Passives")
      )
      (libsource (lib "Altium Content Vault") (part "CAP-NP-2"))
    )
    (comp (ref "C212")
      (value "GRM033R60J104KE19D")
      (footprint "CAPC0603X33X15LL03T05")
      (description "Chip Capacitor, 100 nF, +/- 10%, 6.3 V, -55 to 85 degC, 0201 (0603 Metric), RoHS, Tape and Reel")
      (fields
        (field (name "TOLERANCE") "10%")
        (field (name "CAPACITANCE") "100 nF")
        (field (name "MANUFACTURER") "Basic Passives")
      )
      (libsource (lib "Altium Content Vault") (part "CAP-NP-2"))
    )
    (comp (ref "C213")
      (value "GRM033R60J104KE19D")
      (footprint "CAPC0603X33X15LL03T05")
      (description "Chip Capacitor, 100 nF, +/- 10%, 6.3 V, -55 to 85 degC, 0201 (0603 Metric), RoHS, Tape and Reel")
      (fields
        (field (name "TOLERANCE") "10%")
        (field (name "CAPACITANCE") "100 nF")
        (field (name "MANUFACTURER") "Basic Passives")
      )
      (libsource (lib "Altium Content Vault") (part "CAP-NP-2"))
    )
    (comp (ref "C214")
      (value "GRM033R60J104KE19D")
      (footprint "CAPC0603X33X15LL03T05")
      (description "Chip Capacitor, 100 nF, +/- 10%, 6.3 V, -55 to 85 degC, 0201 (0603 Metric), RoHS, Tape and Reel")
      (fields
        (field (name "TOLERANCE") "10%")
        (field (name "CAPACITANCE") "100 nF")
        (field (name "MANUFACTURER") "Basic Passives")
      )
      (libsource (lib "Altium Content Vault") (part "CAP-NP-2"))
    )
    (comp (ref "C215")
      (value "GRM033R60J104KE19D")
      (footprint "CAPC0603X33X15LL03T05")
      (description "Chip Capacitor, 100 nF, +/- 10%, 6.3 V, -55 to 85 degC, 0201 (0603 Metric), RoHS, Tape and Reel")
      (fields
        (field (name "TOLERANCE") "10%")
        (field (name "CAPACITANCE") "100 nF")
        (field (name "MANUFACTURER") "Basic Passives")
      )
      (libsource (lib "Altium Content Vault") (part "CAP-NP-2"))
    )
    (comp (ref "C216")
      (value "GRM033R60J104KE19D")
      (footprint "CAPC0603X33X15LL03T05")
      (description "Chip Capacitor, 100 nF, +/- 10%, 6.3 V, -55 to 85 degC, 0201 (0603 Metric), RoHS, Tape and Reel")
      (fields
        (field (name "TOLERANCE") "10%")
        (field (name "CAPACITANCE") "100 nF")
        (field (name "MANUFACTURER") "Basic Passives")
      )
      (libsource (lib "Altium Content Vault") (part "CAP-NP-2"))
    )
    (comp (ref "C217")
      (value "GRM033R60J104KE19D")
      (footprint "CAPC0603X33X15LL03T05")
      (description "Chip Capacitor, 100 nF, +/- 10%, 6.3 V, -55 to 85 degC, 0201 (0603 Metric), RoHS, Tape and Reel")
      (fields
        (field (name "TOLERANCE") "10%")
        (field (name "CAPACITANCE") "100 nF")
        (field (name "MANUFACTURER") "Basic Passives")
      )
      (libsource (lib "Altium Content Vault") (part "CAP-NP-2"))
    )
    (comp (ref "C218")
      (value "GRM033R60J104KE19D")
      (footprint "CAPC0603X33X15LL03T05")
      (description "Chip Capacitor, 100 nF, +/- 10%, 6.3 V, -55 to 85 degC, 0201 (0603 Metric), RoHS, Tape and Reel")
      (fields
        (field (name "TOLERANCE") "10%")
        (field (name "CAPACITANCE") "100 nF")
        (field (name "MANUFACTURER") "Basic Passives")
      )
      (libsource (lib "Altium Content Vault") (part "CAP-NP-2"))
    )
    (comp (ref "C219")
      (value "GRM033R60J104KE19D")
      (footprint "CAPC0603X33X15LL03T05")
      (description "Chip Capacitor, 100 nF, +/- 10%, 6.3 V, -55 to 85 degC, 0201 (0603 Metric), RoHS, Tape and Reel")
      (fields
        (field (name "TOLERANCE") "10%")
        (field (name "CAPACITANCE") "100 nF")
        (field (name "MANUFACTURER") "Basic Passives")
      )
      (libsource (lib "Altium Content Vault") (part "CAP-NP-2"))
    )
    (comp (ref "C220")
      (value "GRM033R60J104KE19D")
      (footprint "CAPC0603X33X15LL03T05")
      (description "Chip Capacitor, 100 nF, +/- 10%, 6.3 V, -55 to 85 degC, 0201 (0603 Metric), RoHS, Tape and Reel")
      (fields
        (field (name "TOLERANCE") "10%")
        (field (name "CAPACITANCE") "100 nF")
        (field (name "MANUFACTURER") "Basic Passives")
      )
      (libsource (lib "Altium Content Vault") (part "CAP-NP-2"))
    )
    (comp (ref "C221")
      (value "GRM033R60J104KE19D")
      (footprint "CAPC0603X33X15LL03T05")
      (description "Chip Capacitor, 100 nF, +/- 10%, 6.3 V, -55 to 85 degC, 0201 (0603 Metric), RoHS, Tape and Reel")
      (fields
        (field (name "TOLERANCE") "10%")
        (field (name "CAPACITANCE") "100 nF")
        (field (name "MANUFACTURER") "Basic Passives")
      )
      (libsource (lib "Altium Content Vault") (part "CAP-NP-2"))
    )
    (comp (ref "C222")
      (value "GRM033R60J104KE19D")
      (footprint "CAPC0603X33X15LL03T05")
      (description "Chip Capacitor, 100 nF, +/- 10%, 6.3 V, -55 to 85 degC, 0201 (0603 Metric), RoHS, Tape and Reel")
      (fields
        (field (name "TOLERANCE") "10%")
        (field (name "CAPACITANCE") "100 nF")
        (field (name "MANUFACTURER") "Basic Passives")
      )
      (libsource (lib "Altium Content Vault") (part "CAP-NP-2"))
    )
    (comp (ref "C223")
      (value "GRM033R60J104KE19D")
      (footprint "CAPC0603X33X15LL03T05")
      (description "Chip Capacitor, 100 nF, +/- 10%, 6.3 V, -55 to 85 degC, 0201 (0603 Metric), RoHS, Tape and Reel")
      (fields
        (field (name "TOLERANCE") "10%")
        (field (name "CAPACITANCE") "100 nF")
        (field (name "MANUFACTURER") "Basic Passives")
      )
      (libsource (lib "Altium Content Vault") (part "CAP-NP-2"))
    )
    (comp (ref "C224")
      (value "GRM033R60J104KE19D")
      (footprint "CAPC0603X33X15LL03T05")
      (description "Chip Capacitor, 100 nF, +/- 10%, 6.3 V, -55 to 85 degC, 0201 (0603 Metric), RoHS, Tape and Reel")
      (fields
        (field (name "TOLERANCE") "10%")
        (field (name "CAPACITANCE") "100 nF")
        (field (name "MANUFACTURER") "Basic Passives")
      )
      (libsource (lib "Altium Content Vault") (part "CAP-NP-2"))
    )
    (comp (ref "C225")
      (value "GRM033R60J104KE19D")
      (footprint "CAPC0603X33X15LL03T05")
      (description "Chip Capacitor, 100 nF, +/- 10%, 6.3 V, -55 to 85 degC, 0201 (0603 Metric), RoHS, Tape and Reel")
      (fields
        (field (name "TOLERANCE") "10%")
        (field (name "CAPACITANCE") "100 nF")
        (field (name "MANUFACTURER") "Basic Passives")
      )
      (libsource (lib "Altium Content Vault") (part "CAP-NP-2"))
    )
    (comp (ref "C226")
      (value "GRM033R60J104KE19D")
      (footprint "CAPC0603X33X15LL03T05")
      (description "Chip Capacitor, 100 nF, +/- 10%, 6.3 V, -55 to 85 degC, 0201 (0603 Metric), RoHS, Tape and Reel")
      (fields
        (field (name "TOLERANCE") "10%")
        (field (name "CAPACITANCE") "100 nF")
        (field (name "MANUFACTURER") "Basic Passives")
      )
      (libsource (lib "Altium Content Vault") (part "CAP-NP-2"))
    )
    (comp (ref "C227")
      (value "GRM033R60J104KE19D")
      (footprint "CAPC0603X33X15LL03T05")
      (description "Chip Capacitor, 100 nF, +/- 10%, 6.3 V, -55 to 85 degC, 0201 (0603 Metric), RoHS, Tape and Reel")
      (fields
        (field (name "TOLERANCE") "10%")
        (field (name "CAPACITANCE") "100 nF")
        (field (name "MANUFACTURER") "Basic Passives")
      )
      (libsource (lib "Altium Content Vault") (part "CAP-NP-2"))
    )
    (comp (ref "C228")
      (value "GRM033R60J104KE19D")
      (footprint "CAPC0603X33X15LL03T05")
      (description "Chip Capacitor, 100 nF, +/- 10%, 6.3 V, -55 to 85 degC, 0201 (0603 Metric), RoHS, Tape and Reel")
      (fields
        (field (name "TOLERANCE") "10%")
        (field (name "CAPACITANCE") "100 nF")
        (field (name "MANUFACTURER") "Basic Passives")
      )
      (libsource (lib "Altium Content Vault") (part "CAP-NP-2"))
    )
    (comp (ref "C229")
      (value "GRM033R60J104KE19D")
      (footprint "CAPC0603X33X15LL03T05")
      (description "Chip Capacitor, 100 nF, +/- 10%, 6.3 V, -55 to 85 degC, 0201 (0603 Metric), RoHS, Tape and Reel")
      (fields
        (field (name "TOLERANCE") "10%")
        (field (name "CAPACITANCE") "100 nF")
        (field (name "MANUFACTURER") "Basic Passives")
      )
      (libsource (lib "Altium Content Vault") (part "CAP-NP-2"))
    )
    (comp (ref "C230")
      (value "GRM033R60J104KE19D")
      (footprint "CAPC0603X33X15LL03T05")
      (description "Chip Capacitor, 100 nF, +/- 10%, 6.3 V, -55 to 85 degC, 0201 (0603 Metric), RoHS, Tape and Reel")
      (fields
        (field (name "TOLERANCE") "10%")
        (field (name "CAPACITANCE") "100 nF")
        (field (name "MANUFACTURER") "Basic Passives")
      )
      (libsource (lib "Altium Content Vault") (part "CAP-NP-2"))
    )
    (comp (ref "C231")
      (value "GRM033R60J104KE19D")
      (footprint "CAPC0603X33X15LL03T05")
      (description "Chip Capacitor, 100 nF, +/- 10%, 6.3 V, -55 to 85 degC, 0201 (0603 Metric), RoHS, Tape and Reel")
      (fields
        (field (name "TOLERANCE") "10%")
        (field (name "CAPACITANCE") "100 nF")
        (field (name "MANUFACTURER") "Basic Passives")
      )
      (libsource (lib "Altium Content Vault") (part "CAP-NP-2"))
    )
    (comp (ref "C232")
      (value "GRM033R60J104KE19D")
      (footprint "CAPC0603X33X15LL03T05")
      (description "Chip Capacitor, 100 nF, +/- 10%, 6.3 V, -55 to 85 degC, 0201 (0603 Metric), RoHS, Tape and Reel")
      (fields
        (field (name "TOLERANCE") "10%")
        (field (name "CAPACITANCE") "100 nF")
        (field (name "MANUFACTURER") "Basic Passives")
      )
      (libsource (lib "Altium Content Vault") (part "CAP-NP-2"))
    )
    (comp (ref "C233")
      (value "GRM033R60J104KE19D")
      (footprint "CAPC0603X33X15LL03T05")
      (description "Chip Capacitor, 100 nF, +/- 10%, 6.3 V, -55 to 85 degC, 0201 (0603 Metric), RoHS, Tape and Reel")
      (fields
        (field (name "TOLERANCE") "10%")
        (field (name "CAPACITANCE") "100 nF")
        (field (name "MANUFACTURER") "Basic Passives")
      )
      (libsource (lib "Altium Content Vault") (part "CAP-NP-2"))
    )
    (comp (ref "C234")
      (value "GRM033R60J104KE19D")
      (footprint "CAPC0603X33X15LL03T05")
      (description "Chip Capacitor, 100 nF, +/- 10%, 6.3 V, -55 to 85 degC, 0201 (0603 Metric), RoHS, Tape and Reel")
      (fields
        (field (name "TOLERANCE") "10%")
        (field (name "CAPACITANCE") "100 nF")
        (field (name "MANUFACTURER") "Basic Passives")
      )
      (libsource (lib "Altium Content Vault") (part "CAP-NP-2"))
    )
    (comp (ref "C235")
      (value "GRM033R60J104KE19D")
      (footprint "CAPC0603X33X15LL03T05")
      (description "Chip Capacitor, 100 nF, +/- 10%, 6.3 V, -55 to 85 degC, 0201 (0603 Metric), RoHS, Tape and Reel")
      (fields
        (field (name "TOLERANCE") "10%")
        (field (name "CAPACITANCE") "100 nF")
        (field (name "MANUFACTURER") "Basic Passives")
      )
      (libsource (lib "Altium Content Vault") (part "CAP-NP-2"))
    )
    (comp (ref "C236")
      (value "GRM033R60J104KE19D")
      (footprint "CAPC0603X33X15LL03T05")
      (description "Chip Capacitor, 100 nF, +/- 10%, 6.3 V, -55 to 85 degC, 0201 (0603 Metric), RoHS, Tape and Reel")
      (fields
        (field (name "TOLERANCE") "10%")
        (field (name "CAPACITANCE") "100 nF")
        (field (name "MANUFACTURER") "Basic Passives")
      )
      (libsource (lib "Altium Content Vault") (part "CAP-NP-2"))
    )
    (comp (ref "C237")
      (value "GRM033R60J104KE19D")
      (footprint "CAPC0603X33X15LL03T05")
      (description "Chip Capacitor, 100 nF, +/- 10%, 6.3 V, -55 to 85 degC, 0201 (0603 Metric), RoHS, Tape and Reel")
      (fields
        (field (name "TOLERANCE") "10%")
        (field (name "CAPACITANCE") "100 nF")
        (field (name "MANUFACTURER") "Basic Passives")
      )
      (libsource (lib "Altium Content Vault") (part "CAP-NP-2"))
    )
    (comp (ref "C238")
      (value "GRM033R60J104KE19D")
      (footprint "CAPC0603X33X15LL03T05")
      (description "Chip Capacitor, 100 nF, +/- 10%, 6.3 V, -55 to 85 degC, 0201 (0603 Metric), RoHS, Tape and Reel")
      (fields
        (field (name "TOLERANCE") "10%")
        (field (name "CAPACITANCE") "100 nF")
        (field (name "MANUFACTURER") "Basic Passives")
      )
      (libsource (lib "Altium Content Vault") (part "CAP-NP-2"))
    )
    (comp (ref "C239")
      (value "GRM033R60J104KE19D")
      (footprint "CAPC0603X33X15LL03T05")
      (description "Chip Capacitor, 100 nF, +/- 10%, 6.3 V, -55 to 85 degC, 0201 (0603 Metric), RoHS, Tape and Reel")
      (fields
        (field (name "TOLERANCE") "10%")
        (field (name "CAPACITANCE") "100 nF")
        (field (name "MANUFACTURER") "Basic Passives")
      )
      (libsource (lib "Altium Content Vault") (part "CAP-NP-2"))
    )
    (comp (ref "C240")
      (value "GRM033R60J104KE19D")
      (footprint "CAPC0603X33X15LL03T05")
      (description "Chip Capacitor, 100 nF, +/- 10%, 6.3 V, -55 to 85 degC, 0201 (0603 Metric), RoHS, Tape and Reel")
      (fields
        (field (name "TOLERANCE") "10%")
        (field (name "CAPACITANCE") "100 nF")
        (field (name "MANUFACTURER") "Basic Passives")
      )
      (libsource (lib "Altium Content Vault") (part "CAP-NP-2"))
    )
    (comp (ref "C241")
      (value "GRM033R60J104KE19D")
      (footprint "CAPC0603X33X15LL03T05")
      (description "Chip Capacitor, 100 nF, +/- 10%, 6.3 V, -55 to 85 degC, 0201 (0603 Metric), RoHS, Tape and Reel")
      (fields
        (field (name "TOLERANCE") "10%")
        (field (name "CAPACITANCE") "100 nF")
        (field (name "MANUFACTURER") "Basic Passives")
      )
      (libsource (lib "Altium Content Vault") (part "CAP-NP-2"))
    )
    (comp (ref "C242")
      (value "GRM033R60J104KE19D")
      (footprint "CAPC0603X33X15LL03T05")
      (description "Chip Capacitor, 100 nF, +/- 10%, 6.3 V, -55 to 85 degC, 0201 (0603 Metric), RoHS, Tape and Reel")
      (fields
        (field (name "TOLERANCE") "10%")
        (field (name "CAPACITANCE") "100 nF")
        (field (name "MANUFACTURER") "Basic Passives")
      )
      (libsource (lib "Altium Content Vault") (part "CAP-NP-2"))
    )
    (comp (ref "C243")
      (value "GRM033R60J104KE19D")
      (footprint "CAPC0603X33X15LL03T05")
      (description "Chip Capacitor, 100 nF, +/- 10%, 6.3 V, -55 to 85 degC, 0201 (0603 Metric), RoHS, Tape and Reel")
      (fields
        (field (name "TOLERANCE") "10%")
        (field (name "CAPACITANCE") "100 nF")
        (field (name "MANUFACTURER") "Basic Passives")
      )
      (libsource (lib "Altium Content Vault") (part "CAP-NP-2"))
    )
    (comp (ref "C244")
      (value "GRM033R60J104KE19D")
      (footprint "CAPC0603X33X15LL03T05")
      (description "Chip Capacitor, 100 nF, +/- 10%, 6.3 V, -55 to 85 degC, 0201 (0603 Metric), RoHS, Tape and Reel")
      (fields
        (field (name "TOLERANCE") "10%")
        (field (name "CAPACITANCE") "100 nF")
        (field (name "MANUFACTURER") "Basic Passives")
      )
      (libsource (lib "Altium Content Vault") (part "CAP-NP-2"))
    )
    (comp (ref "C245")
      (value "GRM033R60J104KE19D")
      (footprint "CAPC0603X33X15LL03T05")
      (description "Chip Capacitor, 100 nF, +/- 10%, 6.3 V, -55 to 85 degC, 0201 (0603 Metric), RoHS, Tape and Reel")
      (fields
        (field (name "TOLERANCE") "10%")
        (field (name "CAPACITANCE") "100 nF")
        (field (name "MANUFACTURER") "Basic Passives")
      )
      (libsource (lib "Altium Content Vault") (part "CAP-NP-2"))
    )
    (comp (ref "C246")
      (value "GRM033R60J104KE19D")
      (footprint "CAPC0603X33X15LL03T05")
      (description "Chip Capacitor, 100 nF, +/- 10%, 6.3 V, -55 to 85 degC, 0201 (0603 Metric), RoHS, Tape and Reel")
      (fields
        (field (name "TOLERANCE") "10%")
        (field (name "CAPACITANCE") "100 nF")
        (field (name "MANUFACTURER") "Basic Passives")
      )
      (libsource (lib "Altium Content Vault") (part "CAP-NP-2"))
    )
    (comp (ref "C247")
      (value "GRM033R60J104KE19D")
      (footprint "CAPC0603X33X15LL03T05")
      (description "Chip Capacitor, 100 nF, +/- 10%, 6.3 V, -55 to 85 degC, 0201 (0603 Metric), RoHS, Tape and Reel")
      (fields
        (field (name "TOLERANCE") "10%")
        (field (name "CAPACITANCE") "100 nF")
        (field (name "MANUFACTURER") "Basic Passives")
      )
      (libsource (lib "Altium Content Vault") (part "CAP-NP-2"))
    )
    (comp (ref "C248")
      (value "GRM033R60J104KE19D")
      (footprint "CAPC0603X33X15LL03T05")
      (description "Chip Capacitor, 100 nF, +/- 10%, 6.3 V, -55 to 85 degC, 0201 (0603 Metric), RoHS, Tape and Reel")
      (fields
        (field (name "TOLERANCE") "10%")
        (field (name "CAPACITANCE") "100 nF")
        (field (name "MANUFACTURER") "Basic Passives")
      )
      (libsource (lib "Altium Content Vault") (part "CAP-NP-2"))
    )
    (comp (ref "C249")
      (value "GRM033R60J104KE19D")
      (footprint "CAPC0603X33X15LL03T05")
      (description "Chip Capacitor, 100 nF, +/- 10%, 6.3 V, -55 to 85 degC, 0201 (0603 Metric), RoHS, Tape and Reel")
      (fields
        (field (name "TOLERANCE") "10%")
        (field (name "CAPACITANCE") "100 nF")
        (field (name "MANUFACTURER") "Basic Passives")
      )
      (libsource (lib "Altium Content Vault") (part "CAP-NP-2"))
    )
    (comp (ref "C250")
      (value "GRM033R60J104KE19D")
      (footprint "CAPC0603X33X15LL03T05")
      (description "Chip Capacitor, 100 nF, +/- 10%, 6.3 V, -55 to 85 degC, 0201 (0603 Metric), RoHS, Tape and Reel")
      (fields
        (field (name "TOLERANCE") "10%")
        (field (name "CAPACITANCE") "100 nF")
        (field (name "MANUFACTURER") "Basic Passives")
      )
      (libsource (lib "Altium Content Vault") (part "CAP-NP-2"))
    )
    (comp (ref "C251")
      (value "GRM033R60J104KE19D")
      (footprint "CAPC0603X33X15LL03T05")
      (description "Chip Capacitor, 100 nF, +/- 10%, 6.3 V, -55 to 85 degC, 0201 (0603 Metric), RoHS, Tape and Reel")
      (fields
        (field (name "TOLERANCE") "10%")
        (field (name "CAPACITANCE") "100 nF")
        (field (name "MANUFACTURER") "Basic Passives")
      )
      (libsource (lib "Altium Content Vault") (part "CAP-NP-2"))
    )
    (comp (ref "C252")
      (value "GRM033R60J104KE19D")
      (footprint "CAPC0603X33X15LL03T05")
      (description "Chip Capacitor, 100 nF, +/- 10%, 6.3 V, -55 to 85 degC, 0201 (0603 Metric), RoHS, Tape and Reel")
      (fields
        (field (name "TOLERANCE") "10%")
        (field (name "CAPACITANCE") "100 nF")
        (field (name "MANUFACTURER") "Basic Passives")
      )
      (libsource (lib "Altium Content Vault") (part "CAP-NP-2"))
    )
    (comp (ref "C253")
      (value "GRM033R60J104KE19D")
      (footprint "CAPC0603X33X15LL03T05")
      (description "Chip Capacitor, 100 nF, +/- 10%, 6.3 V, -55 to 85 degC, 0201 (0603 Metric), RoHS, Tape and Reel")
      (fields
        (field (name "TOLERANCE") "10%")
        (field (name "CAPACITANCE") "100 nF")
        (field (name "MANUFACTURER") "Basic Passives")
      )
      (libsource (lib "Altium Content Vault") (part "CAP-NP-2"))
    )
    (comp (ref "C254")
      (value "GRM033R60J104KE19D")
      (footprint "CAPC0603X33X15LL03T05")
      (description "Chip Capacitor, 100 nF, +/- 10%, 6.3 V, -55 to 85 degC, 0201 (0603 Metric), RoHS, Tape and Reel")
      (fields
        (field (name "TOLERANCE") "10%")
        (field (name "CAPACITANCE") "100 nF")
        (field (name "MANUFACTURER") "Basic Passives")
      )
      (libsource (lib "Altium Content Vault") (part "CAP-NP-2"))
    )
    (comp (ref "C255")
      (value "GRM033R60J104KE19D")
      (footprint "CAPC0603X33X15LL03T05")
      (description "Chip Capacitor, 100 nF, +/- 10%, 6.3 V, -55 to 85 degC, 0201 (0603 Metric), RoHS, Tape and Reel")
      (fields
        (field (name "TOLERANCE") "10%")
        (field (name "CAPACITANCE") "100 nF")
        (field (name "MANUFACTURER") "Basic Passives")
      )
      (libsource (lib "Altium Content Vault") (part "CAP-NP-2"))
    )
    (comp (ref "C256")
      (value "GRM033R60J104KE19D")
      (footprint "CAPC0603X33X15LL03T05")
      (description "Chip Capacitor, 100 nF, +/- 10%, 6.3 V, -55 to 85 degC, 0201 (0603 Metric), RoHS, Tape and Reel")
      (fields
        (field (name "TOLERANCE") "10%")
        (field (name "CAPACITANCE") "100 nF")
        (field (name "MANUFACTURER") "Basic Passives")
      )
      (libsource (lib "Altium Content Vault") (part "CAP-NP-2"))
    )
    (comp (ref "C257")
      (value "GRM033R60J104KE19D")
      (footprint "CAPC0603X33X15LL03T05")
      (description "Chip Capacitor, 100 nF, +/- 10%, 6.3 V, -55 to 85 degC, 0201 (0603 Metric), RoHS, Tape and Reel")
      (fields
        (field (name "TOLERANCE") "10%")
        (field (name "CAPACITANCE") "100 nF")
        (field (name "MANUFACTURER") "Basic Passives")
      )
      (libsource (lib "Altium Content Vault") (part "CAP-NP-2"))
    )
    (comp (ref "C258")
      (value "GRM033R60J104KE19D")
      (footprint "CAPC0603X33X15LL03T05")
      (description "Chip Capacitor, 100 nF, +/- 10%, 6.3 V, -55 to 85 degC, 0201 (0603 Metric), RoHS, Tape and Reel")
      (fields
        (field (name "TOLERANCE") "10%")
        (field (name "CAPACITANCE") "100 nF")
        (field (name "MANUFACTURER") "Basic Passives")
      )
      (libsource (lib "Altium Content Vault") (part "CAP-NP-2"))
    )
    (comp (ref "C259")
      (value "GRM033R60J104KE19D")
      (footprint "CAPC0603X33X15LL03T05")
      (description "Chip Capacitor, 100 nF, +/- 10%, 6.3 V, -55 to 85 degC, 0201 (0603 Metric), RoHS, Tape and Reel")
      (fields
        (field (name "TOLERANCE") "10%")
        (field (name "CAPACITANCE") "100 nF")
        (field (name "MANUFACTURER") "Basic Passives")
      )
      (libsource (lib "Altium Content Vault") (part "CAP-NP-2"))
    )
    (comp (ref "C260")
      (value "GRM033R60J104KE19D")
      (footprint "CAPC0603X33X15LL03T05")
      (description "Chip Capacitor, 100 nF, +/- 10%, 6.3 V, -55 to 85 degC, 0201 (0603 Metric), RoHS, Tape and Reel")
      (fields
        (field (name "TOLERANCE") "10%")
        (field (name "CAPACITANCE") "100 nF")
        (field (name "MANUFACTURER") "Basic Passives")
      )
      (libsource (lib "Altium Content Vault") (part "CAP-NP-2"))
    )
    (comp (ref "C261")
      (value "GRM033R60J104KE19D")
      (footprint "CAPC0603X33X15LL03T05")
      (description "Chip Capacitor, 100 nF, +/- 10%, 6.3 V, -55 to 85 degC, 0201 (0603 Metric), RoHS, Tape and Reel")
      (fields
        (field (name "TOLERANCE") "10%")
        (field (name "CAPACITANCE") "100 nF")
        (field (name "MANUFACTURER") "Basic Passives")
      )
      (libsource (lib "Altium Content Vault") (part "CAP-NP-2"))
    )
    (comp (ref "C262")
      (value "GRM033R60J104KE19D")
      (footprint "CAPC0603X33X15LL03T05")
      (description "Chip Capacitor, 100 nF, +/- 10%, 6.3 V, -55 to 85 degC, 0201 (0603 Metric), RoHS, Tape and Reel")
      (fields
        (field (name "TOLERANCE") "10%")
        (field (name "CAPACITANCE") "100 nF")
        (field (name "MANUFACTURER") "Basic Passives")
      )
      (libsource (lib "Altium Content Vault") (part "CAP-NP-2"))
    )
    (comp (ref "C263")
      (value "GRM033R60J104KE19D")
      (footprint "CAPC0603X33X15LL03T05")
      (description "Chip Capacitor, 100 nF, +/- 10%, 6.3 V, -55 to 85 degC, 0201 (0603 Metric), RoHS, Tape and Reel")
      (fields
        (field (name "TOLERANCE") "10%")
        (field (name "CAPACITANCE") "100 nF")
        (field (name "MANUFACTURER") "Basic Passives")
      )
      (libsource (lib "Altium Content Vault") (part "CAP-NP-2"))
    )
  )
  (nets
    (net (code "1") (name "0V95") (class "Default")
      (node (ref "C161") (pin "2") (pinfunction "2_2") (pintype "passive"))
      (node (ref "C162") (pin "2") (pinfunction "2_2") (pintype "passive"))
      (node (ref "C163") (pin "2") (pinfunction "2_2") (pintype "passive"))
      (node (ref "C164") (pin "2") (pinfunction "2_2") (pintype "passive"))
      (node (ref "C165") (pin "2") (pinfunction "2_2") (pintype "passive"))
      (node (ref "C166") (pin "2") (pinfunction "2_2") (pintype "passive"))
      (node (ref "C167") (pin "2") (pinfunction "2_2") (pintype "passive"))
    )
    (net (code "2") (name "A10_0V9") (class "Default")
      (node (ref "C132") (pin "2") (pinfunction "2_2") (pintype "passive"))
      (node (ref "C133") (pin "2") (pinfunction "2_2") (pintype "passive"))
      (node (ref "C134") (pin "2") (pinfunction "2_2") (pintype "passive"))
      (node (ref "C135") (pin "2") (pinfunction "2_2") (pintype "passive"))
      (node (ref "C136") (pin "2") (pinfunction "2_2") (pintype "passive"))
      (node (ref "C137") (pin "2") (pinfunction "2_2") (pintype "passive"))
      (node (ref "C138") (pin "2") (pinfunction "2_2") (pintype "passive"))
      (node (ref "C139") (pin "2") (pinfunction "2_2") (pintype "passive"))
      (node (ref "C140") (pin "2") (pinfunction "2_2") (pintype "passive"))
      (node (ref "C141") (pin "2") (pinfunction "2_2") (pintype "passive"))
      (node (ref "C147") (pin "2") (pinfunction "2_2") (pintype "passive"))
      (node (ref "C148") (pin "2") (pinfunction "2_2") (pintype "passive"))
      (node (ref "C149") (pin "2") (pinfunction "2_2") (pintype "passive"))
      (node (ref "C150") (pin "2") (pinfunction "2_2") (pintype "passive"))
      (node (ref "C151") (pin "2") (pinfunction "2_2") (pintype "passive"))
      (node (ref "C152") (pin "2") (pinfunction "2_2") (pintype "passive"))
      (node (ref "C153") (pin "2") (pinfunction "2_2") (pintype "passive"))
      (node (ref "C154") (pin "2") (pinfunction "2_2") (pintype "passive"))
      (node (ref "C155") (pin "2") (pinfunction "2_2") (pintype "passive"))
      (node (ref "C156") (pin "2") (pinfunction "2_2") (pintype "passive"))
      (node (ref "C157") (pin "2") (pinfunction "2_2") (pintype "passive"))
      (node (ref "C158") (pin "2") (pinfunction "2_2") (pintype "passive"))
      (node (ref "C159") (pin "2") (pinfunction "2_2") (pintype "passive"))
      (node (ref "C160") (pin "2") (pinfunction "2_2") (pintype "passive"))
      (node (ref "C168") (pin "2") (pinfunction "2_2") (pintype "passive"))
      (node (ref "C169") (pin "2") (pinfunction "2_2") (pintype "passive"))
      (node (ref "C170") (pin "2") (pinfunction "2_2") (pintype "passive"))
      (node (ref "C171") (pin "2") (pinfunction "2_2") (pintype "passive"))
      (node (ref "C172") (pin "2") (pinfunction "2_2") (pintype "passive"))
      (node (ref "C173") (pin "2") (pinfunction "2_2") (pintype "passive"))
      (node (ref "C174") (pin "2") (pinfunction "2_2") (pintype "passive"))
      (node (ref "C175") (pin "2") (pinfunction "2_2") (pintype "passive"))
      (node (ref "C176") (pin "2") (pinfunction "2_2") (pintype "passive"))
      (node (ref "C177") (pin "2") (pinfunction "2_2") (pintype "passive"))
      (node (ref "C178") (pin "2") (pinfunction "2_2") (pintype "passive"))
      (node (ref "C179") (pin "2") (pinfunction "2_2") (pintype "passive"))
      (node (ref "C180") (pin "2") (pinfunction "2_2") (pintype "passive"))
      (node (ref "C181") (pin "2") (pinfunction "2_2") (pintype "passive"))
      (node (ref "C182") (pin "2") (pinfunction "2_2") (pintype "passive"))
      (node (ref "C183") (pin "2") (pinfunction "2_2") (pintype "passive"))
      (node (ref "C184") (pin "2") (pinfunction "2_2") (pintype "passive"))
      (node (ref "C185") (pin "2") (pinfunction "2_2") (pintype "passive"))
      (node (ref "C186") (pin "2") (pinfunction "2_2") (pintype "passive"))
      (node (ref "C187") (pin "2") (pinfunction "2_2") (pintype "passive"))
      (node (ref "C188") (pin "2") (pinfunction "2_2") (pintype "passive"))
      (node (ref "C189") (pin "2") (pinfunction "2_2") (pintype "passive"))
      (node (ref "C190") (pin "2") (pinfunction "2_2") (pintype "passive"))
      (node (ref "C191") (pin "2") (pinfunction "2_2") (pintype "passive"))
      (node (ref "C192") (pin "2") (pinfunction "2_2") (pintype "passive"))
      (node (ref "C193") (pin "2") (pinfunction "2_2") (pintype "passive"))
      (node (ref "C194") (pin "2") (pinfunction "2_2") (pintype "passive"))
      (node (ref "C195") (pin "2") (pinfunction "2_2") (pintype "passive"))
      (node (ref "C196") (pin "2") (pinfunction "2_2") (pintype "passive"))
      (node (ref "C197") (pin "2") (pinfunction "2_2") (pintype "passive"))
      (node (ref "C198") (pin "2") (pinfunction "2_2") (pintype "passive"))
      (node (ref "C199") (pin "2") (pinfunction "2_2") (pintype "passive"))
      (node (ref "C200") (pin "2") (pinfunction "2_2") (pintype "passive"))
      (node (ref "C201") (pin "2") (pinfunction "2_2") (pintype "passive"))
      (node (ref "C202") (pin "2") (pinfunction "2_2") (pintype "passive"))
      (node (ref "C203") (pin "2") (pinfunction "2_2") (pintype "passive"))
      (node (ref "C204") (pin "2") (pinfunction "2_2") (pintype "passive"))
      (node (ref "C205") (pin "2") (pinfunction "2_2") (pintype "passive"))
      (node (ref "C206") (pin "2") (pinfunction "2_2") (pintype "passive"))
      (node (ref "C207") (pin "2") (pinfunction "2_2") (pintype "passive"))
      (node (ref "C208") (pin "2") (pinfunction "2_2") (pintype "passive"))
      (node (ref "C209") (pin "2") (pinfunction "2_2") (pintype "passive"))
      (node (ref "C210") (pin "2") (pinfunction "2_2") (pintype "passive"))
      (node (ref "C211") (pin "2") (pinfunction "2_2") (pintype "passive"))
      (node (ref "C212") (pin "2") (pinfunction "2_2") (pintype "passive"))
      (node (ref "C213") (pin "2") (pinfunction "2_2") (pintype "passive"))
      (node (ref "C214") (pin "2") (pinfunction "2_2") (pintype "passive"))
      (node (ref "C215") (pin "2") (pinfunction "2_2") (pintype "passive"))
      (node (ref "C216") (pin "2") (pinfunction "2_2") (pintype "passive"))
      (node (ref "C217") (pin "2") (pinfunction "2_2") (pintype "passive"))
      (node (ref "C218") (pin "2") (pinfunction "2_2") (pintype "passive"))
      (node (ref "C219") (pin "2") (pinfunction "2_2") (pintype "passive"))
      (node (ref "C220") (pin "2") (pinfunction "2_2") (pintype "passive"))
      (node (ref "C221") (pin "2") (pinfunction "2_2") (pintype "passive"))
      (node (ref "C222") (pin "2") (pinfunction "2_2") (pintype "passive"))
      (node (ref "C223") (pin "2") (pinfunction "2_2") (pintype "passive"))
      (node (ref "C224") (pin "2") (pinfunction "2_2") (pintype "passive"))
      (node (ref "C225") (pin "2") (pinfunction "2_2") (pintype "passive"))
      (node (ref "C226") (pin "2") (pinfunction "2_2") (pintype "passive"))
      (node (ref "C227") (pin "2") (pinfunction "2_2") (pintype "passive"))
      (node (ref "C228") (pin "2") (pinfunction "2_2") (pintype "passive"))
      (node (ref "C229") (pin "2") (pinfunction "2_2") (pintype "passive"))
      (node (ref "C230") (pin "2") (pinfunction "2_2") (pintype "passive"))
      (node (ref "C231") (pin "2") (pinfunction "2_2") (pintype "passive"))
      (node (ref "C232") (pin "2") (pinfunction "2_2") (pintype "passive"))
      (node (ref "C233") (pin "2") (pinfunction "2_2") (pintype "passive"))
      (node (ref "C234") (pin "2") (pinfunction "2_2") (pintype "passive"))
      (node (ref "C235") (pin "2") (pinfunction "2_2") (pintype "passive"))
      (node (ref "C236") (pin "2") (pinfunction "2_2") (pintype "passive"))
      (node (ref "C237") (pin "2") (pinfunction "2_2") (pintype "passive"))
      (node (ref "C238") (pin "2") (pinfunction "2_2") (pintype "passive"))
      (node (ref "C239") (pin "2") (pinfunction "2_2") (pintype "passive"))
      (node (ref "C240") (pin "2") (pinfunction "2_2") (pintype "passive"))
      (node (ref "C241") (pin "2") (pinfunction "2_2") (pintype "passive"))
      (node (ref "C242") (pin "2") (pinfunction "2_2") (pintype "passive"))
      (node (ref "C243") (pin "2") (pinfunction "2_2") (pintype "passive"))
      (node (ref "C244") (pin "2") (pinfunction "2_2") (pintype "passive"))
      (node (ref "C245") (pin "2") (pinfunction "2_2") (pintype "passive"))
      (node (ref "C246") (pin "2") (pinfunction "2_2") (pintype "passive"))
      (node (ref "C247") (pin "2") (pinfunction "2_2") (pintype "passive"))
      (node (ref "C248") (pin "2") (pinfunction "2_2") (pintype "passive"))
      (node (ref "C249") (pin "2") (pinfunction "2_2") (pintype "passive"))
      (node (ref "C250") (pin "2") (pinfunction "2_2") (pintype "passive"))
      (node (ref "C251") (pin "2") (pinfunction "2_2") (pintype "passive"))
      (node (ref "C252") (pin "2") (pinfunction "2_2") (pintype "passive"))
      (node (ref "C253") (pin "2") (pinfunction "2_2") (pintype "passive"))
      (node (ref "C254") (pin "2") (pinfunction "2_2") (pintype "passive"))
      (node (ref "C255") (pin "2") (pinfunction "2_2") (pintype "passive"))
      (node (ref "C256") (pin "2") (pinfunction "2_2") (pintype "passive"))
      (node (ref "C257") (pin "2") (pinfunction "2_2") (pintype "passive"))
      (node (ref "C258") (pin "2") (pinfunction "2_2") (pintype "passive"))
      (node (ref "C259") (pin "2") (pinfunction "2_2") (pintype "passive"))
      (node (ref "C260") (pin "2") (pinfunction "2_2") (pintype "passive"))
      (node (ref "C261") (pin "2") (pinfunction "2_2") (pintype "passive"))
      (node (ref "C262") (pin "2") (pinfunction "2_2") (pintype "passive"))
      (node (ref "C263") (pin "2") (pinfunction "2_2") (pintype "passive"))
    )
    (net (code "3") (name "GND") (class "Default")
      (node (ref "C132") (pin "1") (pinfunction "1_1") (pintype "passive"))
      (node (ref "C133") (pin "1") (pinfunction "1_1") (pintype "passive"))
      (node (ref "C134") (pin "1") (pinfunction "1_1") (pintype "passive"))
      (node (ref "C135") (pin "1") (pinfunction "1_1") (pintype "passive"))
      (node (ref "C136") (pin "1") (pinfunction "1_1") (pintype "passive"))
      (node (ref "C137") (pin "1") (pinfunction "1_1") (pintype "passive"))
      (node (ref "C138") (pin "1") (pinfunction "1_1") (pintype "passive"))
      (node (ref "C139") (pin "1") (pinfunction "1_1") (pintype "passive"))
      (node (ref "C140") (pin "1") (pinfunction "1_1") (pintype "passive"))
      (node (ref "C141") (pin "1") (pinfunction "1_1") (pintype "passive"))
      (node (ref "C142") (pin "1") (pinfunction "1_1") (pintype "passive"))
      (node (ref "C143") (pin "1") (pinfunction "1_1") (pintype "passive"))
      (node (ref "C144") (pin "1") (pinfunction "1_1") (pintype "passive"))
      (node (ref "C145") (pin "1") (pinfunction "1_1") (pintype "passive"))
      (node (ref "C146") (pin "1") (pinfunction "1_1") (pintype "passive"))
      (node (ref "C147") (pin "1") (pinfunction "1_1") (pintype "passive"))
      (node (ref "C148") (pin "1") (pinfunction "1_1") (pintype "passive"))
      (node (ref "C149") (pin "1") (pinfunction "1_1") (pintype "passive"))
      (node (ref "C150") (pin "1") (pinfunction "1_1") (pintype "passive"))
      (node (ref "C151") (pin "1") (pinfunction "1_1") (pintype "passive"))
      (node (ref "C152") (pin "1") (pinfunction "1_1") (pintype "passive"))
      (node (ref "C153") (pin "1") (pinfunction "1_1") (pintype "passive"))
      (node (ref "C154") (pin "1") (pinfunction "1_1") (pintype "passive"))
      (node (ref "C155") (pin "1") (pinfunction "1_1") (pintype "passive"))
      (node (ref "C156") (pin "1") (pinfunction "1_1") (pintype "passive"))
      (node (ref "C157") (pin "1") (pinfunction "1_1") (pintype "passive"))
      (node (ref "C158") (pin "1") (pinfunction "1_1") (pintype "passive"))
      (node (ref "C159") (pin "1") (pinfunction "1_1") (pintype "passive"))
      (node (ref "C160") (pin "1") (pinfunction "1_1") (pintype "passive"))
      (node (ref "C161") (pin "1") (pinfunction "1_1") (pintype "passive"))
      (node (ref "C162") (pin "1") (pinfunction "1_1") (pintype "passive"))
      (node (ref "C163") (pin "1") (pinfunction "1_1") (pintype "passive"))
      (node (ref "C164") (pin "1") (pinfunction "1_1") (pintype "passive"))
      (node (ref "C165") (pin "1") (pinfunction "1_1") (pintype "passive"))
      (node (ref "C166") (pin "1") (pinfunction "1_1") (pintype "passive"))
      (node (ref "C167") (pin "1") (pinfunction "1_1") (pintype "passive"))
      (node (ref "C168") (pin "1") (pinfunction "1_1") (pintype "passive"))
      (node (ref "C169") (pin "1") (pinfunction "1_1") (pintype "passive"))
      (node (ref "C170") (pin "1") (pinfunction "1_1") (pintype "passive"))
      (node (ref "C171") (pin "1") (pinfunction "1_1") (pintype "passive"))
      (node (ref "C172") (pin "1") (pinfunction "1_1") (pintype "passive"))
      (node (ref "C173") (pin "1") (pinfunction "1_1") (pintype "passive"))
      (node (ref "C174") (pin "1") (pinfunction "1_1") (pintype "passive"))
      (node (ref "C175") (pin "1") (pinfunction "1_1") (pintype "passive"))
      (node (ref "C176") (pin "1") (pinfunction "1_1") (pintype "passive"))
      (node (ref "C177") (pin "1") (pinfunction "1_1") (pintype "passive"))
      (node (ref "C178") (pin "1") (pinfunction "1_1") (pintype "passive"))
      (node (ref "C179") (pin "1") (pinfunction "1_1") (pintype "passive"))
      (node (ref "C180") (pin "1") (pinfunction "1_1") (pintype "passive"))
      (node (ref "C181") (pin "1") (pinfunction "1_1") (pintype "passive"))
      (node (ref "C182") (pin "1") (pinfunction "1_1") (pintype "passive"))
      (node (ref "C183") (pin "1") (pinfunction "1_1") (pintype "passive"))
      (node (ref "C184") (pin "1") (pinfunction "1_1") (pintype "passive"))
      (node (ref "C185") (pin "1") (pinfunction "1_1") (pintype "passive"))
      (node (ref "C186") (pin "1") (pinfunction "1_1") (pintype "passive"))
      (node (ref "C187") (pin "1") (pinfunction "1_1") (pintype "passive"))
      (node (ref "C188") (pin "1") (pinfunction "1_1") (pintype "passive"))
      (node (ref "C189") (pin "1") (pinfunction "1_1") (pintype "passive"))
      (node (ref "C190") (pin "1") (pinfunction "1_1") (pintype "passive"))
      (node (ref "C191") (pin "1") (pinfunction "1_1") (pintype "passive"))
      (node (ref "C192") (pin "1") (pinfunction "1_1") (pintype "passive"))
      (node (ref "C193") (pin "1") (pinfunction "1_1") (pintype "passive"))
      (node (ref "C194") (pin "1") (pinfunction "1_1") (pintype "passive"))
      (node (ref "C195") (pin "1") (pinfunction "1_1") (pintype "passive"))
      (node (ref "C196") (pin "1") (pinfunction "1_1") (pintype "passive"))
      (node (ref "C197") (pin "1") (pinfunction "1_1") (pintype "passive"))
      (node (ref "C198") (pin "1") (pinfunction "1_1") (pintype "passive"))
      (node (ref "C199") (pin "1") (pinfunction "1_1") (pintype "passive"))
      (node (ref "C200") (pin "1") (pinfunction "1_1") (pintype "passive"))
      (node (ref "C201") (pin "1") (pinfunction "1_1") (pintype "passive"))
      (node (ref "C202") (pin "1") (pinfunction "1_1") (pintype "passive"))
      (node (ref "C203") (pin "1") (pinfunction "1_1") (pintype "passive"))
      (node (ref "C204") (pin "1") (pinfunction "1_1") (pintype "passive"))
      (node (ref "C205") (pin "1") (pinfunction "1_1") (pintype "passive"))
      (node (ref "C206") (pin "1") (pinfunction "1_1") (pintype "passive"))
      (node (ref "C207") (pin "1") (pinfunction "1_1") (pintype "passive"))
      (node (ref "C208") (pin "1") (pinfunction "1_1") (pintype "passive"))
      (node (ref "C209") (pin "1") (pinfunction "1_1") (pintype "passive"))
      (node (ref "C210") (pin "1") (pinfunction "1_1") (pintype "passive"))
      (node (ref "C211") (pin "1") (pinfunction "1_1") (pintype "passive"))
      (node (ref "C212") (pin "1") (pinfunction "1_1") (pintype "passive"))
      (node (ref "C213") (pin "1") (pinfunction "1_1") (pintype "passive"))
      (node (ref "C214") (pin "1") (pinfunction "1_1") (pintype "passive"))
      (node (ref "C215") (pin "1") (pinfunction "1_1") (pintype "passive"))
      (node (ref "C216") (pin "1") (pinfunction "1_1") (pintype "passive"))
      (node (ref "C217") (pin "1") (pinfunction "1_1") (pintype "passive"))
      (node (ref "C218") (pin "1") (pinfunction "1_1") (pintype "passive"))
      (node (ref "C219") (pin "1") (pinfunction "1_1") (pintype "passive"))
      (node (ref "C220") (pin "1") (pinfunction "1_1") (pintype "passive"))
      (node (ref "C221") (pin "1") (pinfunction "1_1") (pintype "passive"))
      (node (ref "C222") (pin "1") (pinfunction "1_1") (pintype "passive"))
      (node (ref "C223") (pin "1") (pinfunction "1_1") (pintype "passive"))
      (node (ref "C224") (pin "1") (pinfunction "1_1") (pintype "passive"))
      (node (ref "C225") (pin "1") (pinfunction "1_1") (pintype "passive"))
      (node (ref "C226") (pin "1") (pinfunction "1_1") (pintype "passive"))
      (node (ref "C227") (pin "1") (pinfunction "1_1") (pintype "passive"))
      (node (ref "C228") (pin "1") (pinfunction "1_1") (pintype "passive"))
      (node (ref "C229") (pin "1") (pinfunction "1_1") (pintype "passive"))
      (node (ref "C230") (pin "1") (pinfunction "1_1") (pintype "passive"))
      (node (ref "C231") (pin "1") (pinfunction "1_1") (pintype "passive"))
      (node (ref "C232") (pin "1") (pinfunction "1_1") (pintype "passive"))
      (node (ref "C233") (pin "1") (pinfunction "1_1") (pintype "passive"))
      (node (ref "C234") (pin "1") (pinfunction "1_1") (pintype "passive"))
      (node (ref "C235") (pin "1") (pinfunction "1_1") (pintype "passive"))
      (node (ref "C236") (pin "1") (pinfunction "1_1") (pintype "passive"))
      (node (ref "C237") (pin "1") (pinfunction "1_1") (pintype "passive"))
      (node (ref "C238") (pin "1") (pinfunction "1_1") (pintype "passive"))
      (node (ref "C239") (pin "1") (pinfunction "1_1") (pintype "passive"))
      (node (ref "C240") (pin "1") (pinfunction "1_1") (pintype "passive"))
      (node (ref "C241") (pin "1") (pinfunction "1_1") (pintype "passive"))
      (node (ref "C242") (pin "1") (pinfunction "1_1") (pintype "passive"))
      (node (ref "C243") (pin "1") (pinfunction "1_1") (pintype "passive"))
      (node (ref "C244") (pin "1") (pinfunction "1_1") (pintype "passive"))
      (node (ref "C245") (pin "1") (pinfunction "1_1") (pintype "passive"))
      (node (ref "C246") (pin "1") (pinfunction "1_1") (pintype "passive"))
      (node (ref "C247") (pin "1") (pinfunction "1_1") (pintype "passive"))
      (node (ref "C248") (pin "1") (pinfunction "1_1") (pintype "passive"))
      (node (ref "C249") (pin "1") (pinfunction "1_1") (pintype "passive"))
      (node (ref "C250") (pin "1") (pinfunction "1_1") (pintype "passive"))
      (node (ref "C251") (pin "1") (pinfunction "1_1") (pintype "passive"))
      (node (ref "C252") (pin "1") (pinfunction "1_1") (pintype "passive"))
      (node (ref "C253") (pin "1") (pinfunction "1_1") (pintype "passive"))
      (node (ref "C254") (pin "1") (pinfunction "1_1") (pintype "passive"))
      (node (ref "C255") (pin "1") (pinfunction "1_1") (pintype "passive"))
      (node (ref "C256") (pin "1") (pinfunction "1_1") (pintype "passive"))
      (node (ref "C257") (pin "1") (pinfunction "1_1") (pintype "passive"))
      (node (ref "C258") (pin "1") (pinfunction "1_1") (pintype "passive"))
      (node (ref "C259") (pin "1") (pinfunction "1_1") (pintype "passive"))
      (node (ref "C260") (pin "1") (pinfunction "1_1") (pintype "passive"))
      (node (ref "C261") (pin "1") (pinfunction "1_1") (pintype "passive"))
      (node (ref "C262") (pin "1") (pinfunction "1_1") (pintype "passive"))
      (node (ref "C263") (pin "1") (pinfunction "1_1") (pintype "passive"))
    )
    (net (code "4") (name "HPS_0V95") (class "Default")
      (node (ref "C142") (pin "2") (pinfunction "2_2") (pintype "passive"))
      (node (ref "C143") (pin "2") (pinfunction "2_2") (pintype "passive"))
      (node (ref "C144") (pin "2") (pinfunction "2_2") (pintype "passive"))
      (node (ref "C145") (pin "2") (pinfunction "2_2") (pintype "passive"))
      (node (ref "C146") (pin "2") (pinfunction "2_2") (pintype "passive"))
    )
  )
)
